# CPU_LPC1776.net
KiCad netlist of a schematic drawn in Altium Designer
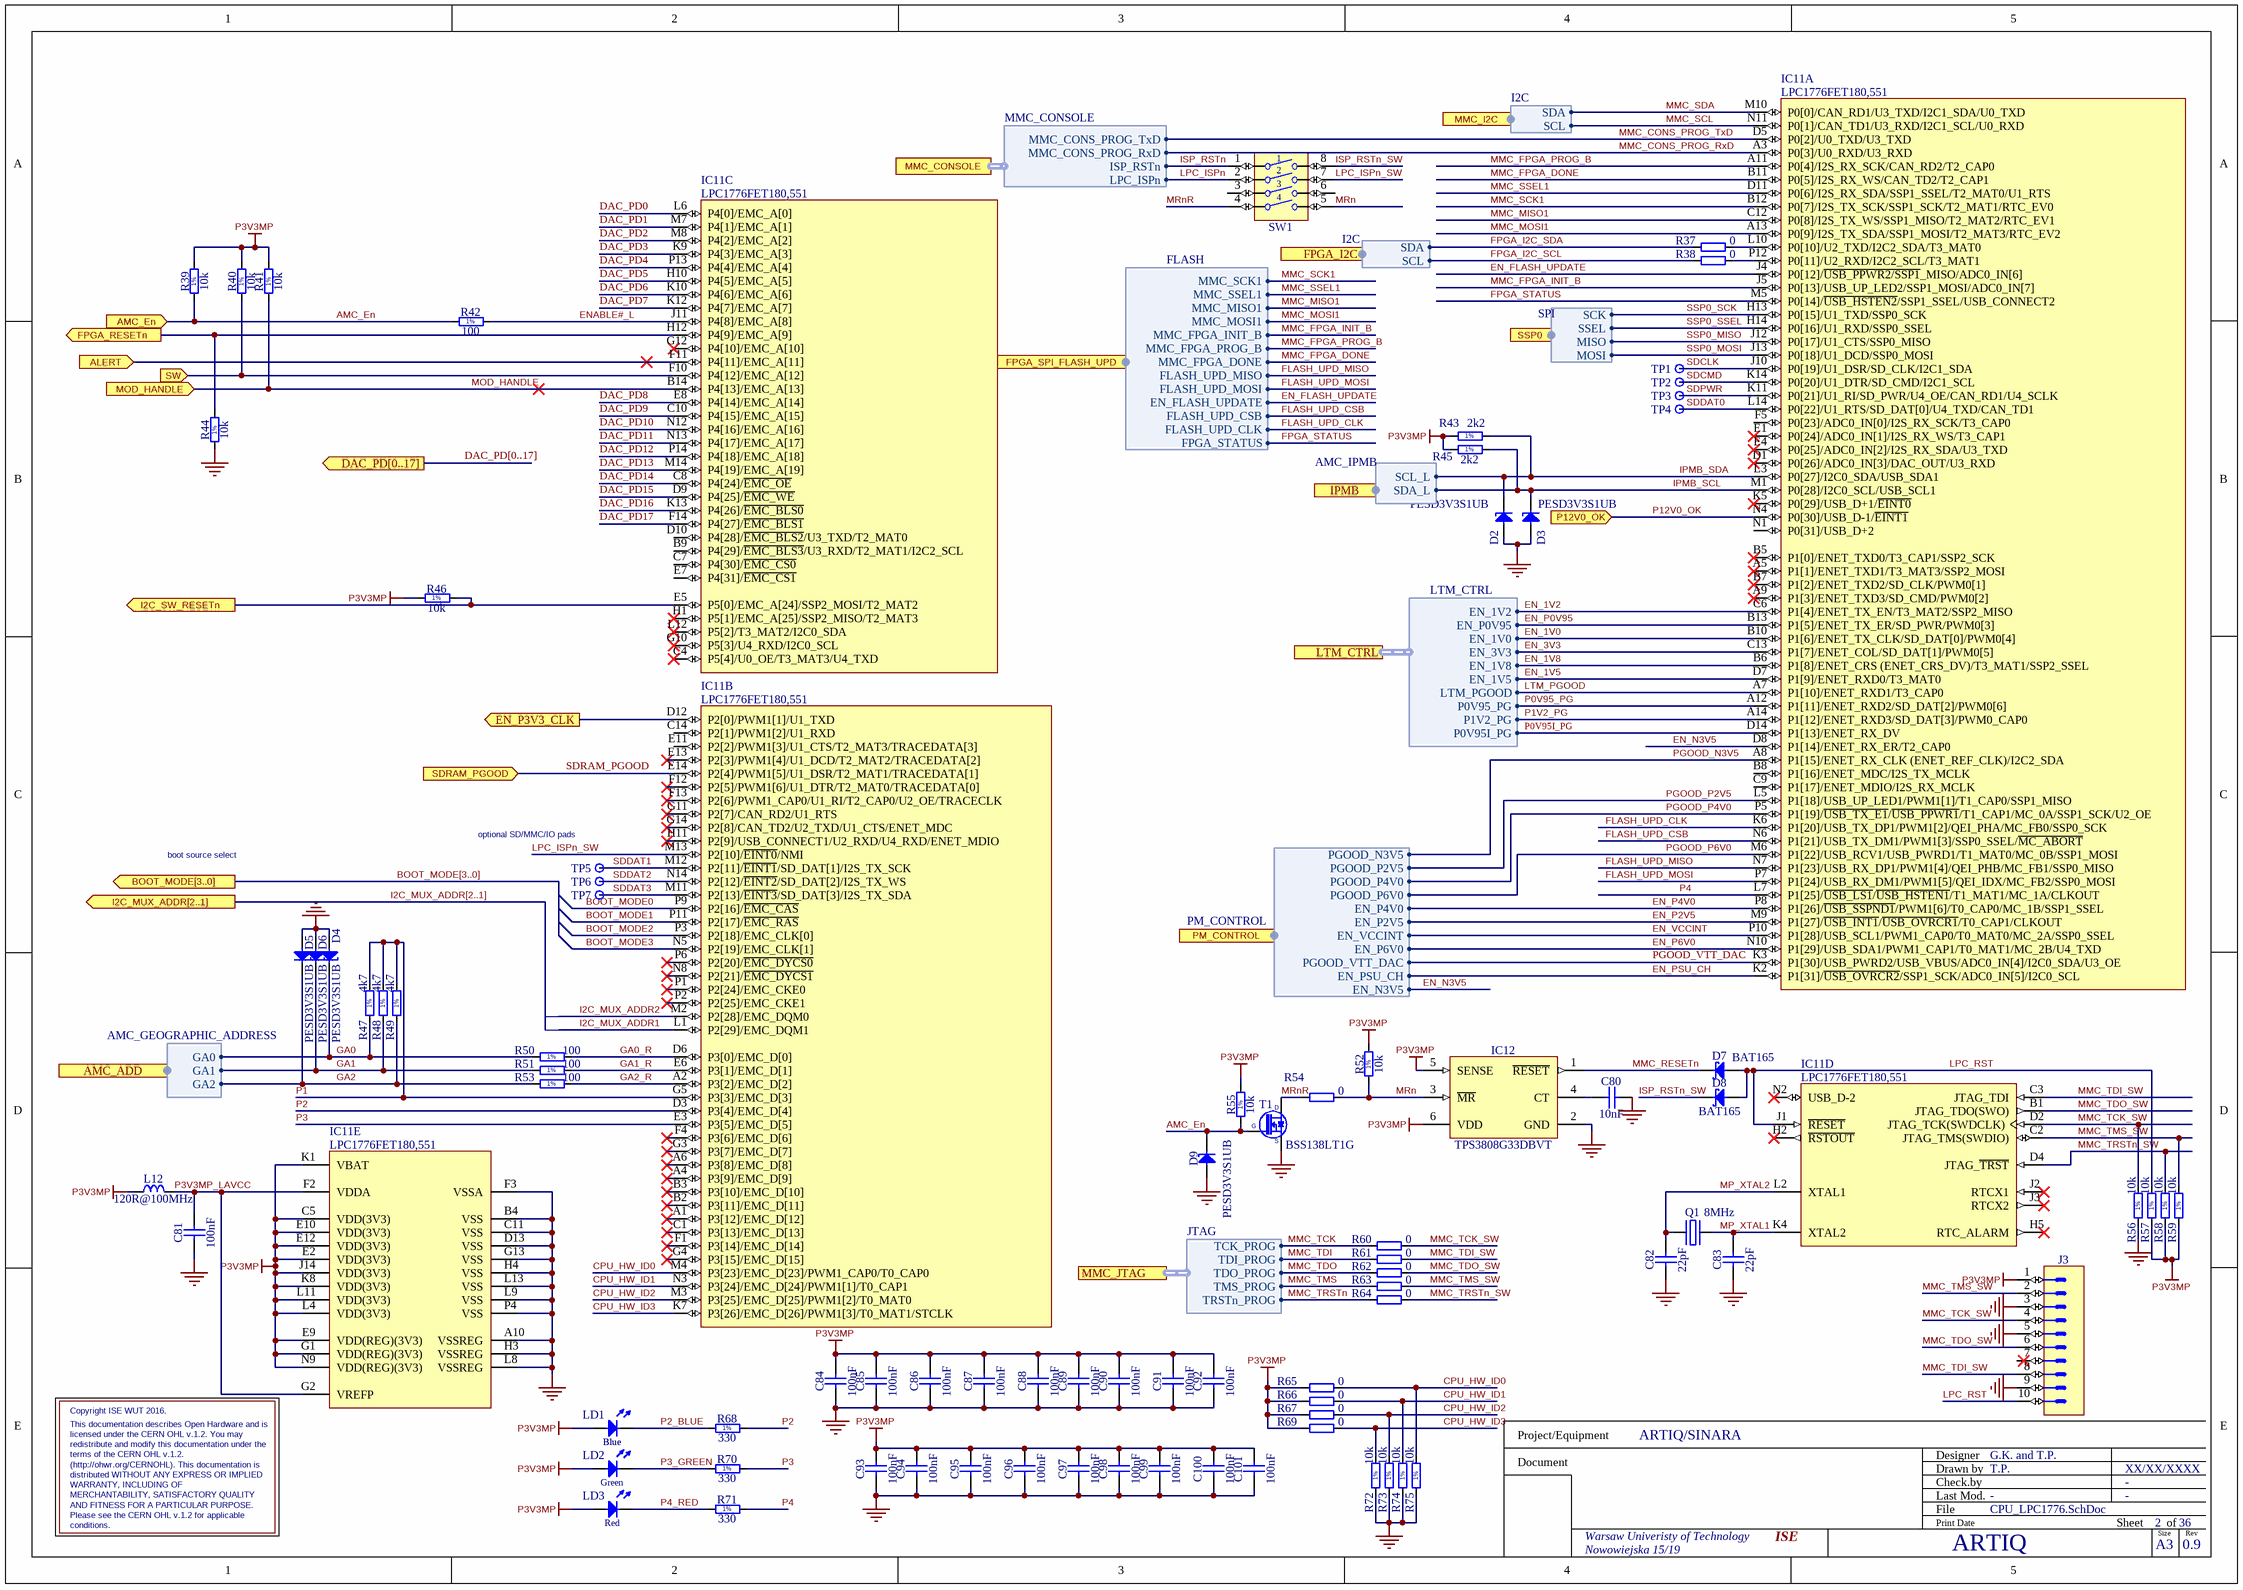
[diagram p0: CPU_LPC1776.SchDoc]

(export (version "E")
  (design (tool "Eeschema 10.0.6"))
  (components
    (comp (ref "C80")
      (value "10nF")
      (footprint "CAPC1005X55N")
      (description "Non-polarised capacitor")
      (fields
        (field (name "MANUFACTURER PART NUMBER") "CC0402_10NF_16V_10%_X7R")
        (field (name "MANUFACTURER") "GENERIC")
        (field (name "AUTHOR") "CERN DEM JLC")
      )
      (libsource (lib "Capacitors") (part "Capacitor - non polarized"))
    )
    (comp (ref "C81")
      (value "100nF")
      (footprint "CAPC0603X33N")
      (description "Non-polarised capacitor")
      (fields
        (field (name "MANUFACTURER PART NUMBER") "CC0201_100NF_6.3V_10%_X5R")
        (field (name "MANUFACTURER") "GENERIC")
        (field (name "AUTHOR") "CERN DEM JLC")
      )
      (libsource (lib "Capacitors") (part "Capacitor - non polarized"))
    )
    (comp (ref "C82")
      (value "22pF")
      (footprint "CAPC1005X55N")
      (description "Non-polarised capacitor")
      (fields
        (field (name "MANUFACTURER PART NUMBER") "CC0402_22PF_50V_5%_C0G")
        (field (name "MANUFACTURER") "GENERIC")
        (field (name "AUTHOR") "CERN DEM JLC")
      )
      (libsource (lib "Capacitors") (part "Capacitor - non polarized"))
    )
    (comp (ref "C83")
      (value "22pF")
      (footprint "CAPC1005X55N")
      (description "Non-polarised capacitor")
      (fields
        (field (name "MANUFACTURER PART NUMBER") "CC0402_22PF_50V_5%_C0G")
        (field (name "MANUFACTURER") "GENERIC")
        (field (name "AUTHOR") "CERN DEM JLC")
      )
      (libsource (lib "Capacitors") (part "Capacitor - non polarized"))
    )
    (comp (ref "C84")
      (value "100nF")
      (footprint "CAPC0603X33N")
      (description "Non-polarised capacitor")
      (fields
        (field (name "MANUFACTURER PART NUMBER") "CC0201_100NF_6.3V_10%_X5R")
        (field (name "MANUFACTURER") "GENERIC")
        (field (name "AUTHOR") "CERN DEM JLC")
      )
      (libsource (lib "Capacitors") (part "Capacitor - non polarized"))
    )
    (comp (ref "C85")
      (value "100nF")
      (footprint "CAPC0603X33N")
      (description "Non-polarised capacitor")
      (fields
        (field (name "MANUFACTURER PART NUMBER") "CC0201_100NF_6.3V_10%_X5R")
        (field (name "MANUFACTURER") "GENERIC")
        (field (name "AUTHOR") "CERN DEM JLC")
      )
      (libsource (lib "Capacitors") (part "Capacitor - non polarized"))
    )
    (comp (ref "C86")
      (value "100nF")
      (footprint "CAPC0603X33N")
      (description "Non-polarised capacitor")
      (fields
        (field (name "MANUFACTURER PART NUMBER") "CC0201_100NF_6.3V_10%_X5R")
        (field (name "MANUFACTURER") "GENERIC")
        (field (name "AUTHOR") "CERN DEM JLC")
      )
      (libsource (lib "Capacitors") (part "Capacitor - non polarized"))
    )
    (comp (ref "C87")
      (value "100nF")
      (footprint "CAPC0603X33N")
      (description "Non-polarised capacitor")
      (fields
        (field (name "MANUFACTURER PART NUMBER") "CC0201_100NF_6.3V_10%_X5R")
        (field (name "MANUFACTURER") "GENERIC")
        (field (name "AUTHOR") "CERN DEM JLC")
      )
      (libsource (lib "Capacitors") (part "Capacitor - non polarized"))
    )
    (comp (ref "C88")
      (value "100nF")
      (footprint "CAPC0603X33N")
      (description "Non-polarised capacitor")
      (fields
        (field (name "MANUFACTURER PART NUMBER") "CC0201_100NF_6.3V_10%_X5R")
        (field (name "MANUFACTURER") "GENERIC")
        (field (name "AUTHOR") "CERN DEM JLC")
      )
      (libsource (lib "Capacitors") (part "Capacitor - non polarized"))
    )
    (comp (ref "C89")
      (value "100nF")
      (footprint "CAPC0603X33N")
      (description "Non-polarised capacitor")
      (fields
        (field (name "MANUFACTURER PART NUMBER") "CC0201_100NF_6.3V_10%_X5R")
        (field (name "MANUFACTURER") "GENERIC")
        (field (name "AUTHOR") "CERN DEM JLC")
      )
      (libsource (lib "Capacitors") (part "Capacitor - non polarized"))
    )
    (comp (ref "C90")
      (value "100nF")
      (footprint "CAPC0603X33N")
      (description "Non-polarised capacitor")
      (fields
        (field (name "MANUFACTURER PART NUMBER") "CC0201_100NF_6.3V_10%_X5R")
        (field (name "MANUFACTURER") "GENERIC")
        (field (name "AUTHOR") "CERN DEM JLC")
      )
      (libsource (lib "Capacitors") (part "Capacitor - non polarized"))
    )
    (comp (ref "C91")
      (value "100nF")
      (footprint "CAPC0603X33N")
      (description "Non-polarised capacitor")
      (fields
        (field (name "MANUFACTURER PART NUMBER") "CC0201_100NF_6.3V_10%_X5R")
        (field (name "MANUFACTURER") "GENERIC")
        (field (name "AUTHOR") "CERN DEM JLC")
      )
      (libsource (lib "Capacitors") (part "Capacitor - non polarized"))
    )
    (comp (ref "C92")
      (value "100nF")
      (footprint "CAPC0603X33N")
      (description "Non-polarised capacitor")
      (fields
        (field (name "MANUFACTURER PART NUMBER") "CC0201_100NF_6.3V_10%_X5R")
        (field (name "MANUFACTURER") "GENERIC")
        (field (name "AUTHOR") "CERN DEM JLC")
      )
      (libsource (lib "Capacitors") (part "Capacitor - non polarized"))
    )
    (comp (ref "C93")
      (value "100nF")
      (footprint "CAPC0603X33N")
      (description "Non-polarised capacitor")
      (fields
        (field (name "MANUFACTURER PART NUMBER") "CC0201_100NF_6.3V_10%_X5R")
        (field (name "MANUFACTURER") "GENERIC")
        (field (name "AUTHOR") "CERN DEM JLC")
      )
      (libsource (lib "Capacitors") (part "Capacitor - non polarized"))
    )
    (comp (ref "C94")
      (value "100nF")
      (footprint "CAPC0603X33N")
      (description "Non-polarised capacitor")
      (fields
        (field (name "MANUFACTURER PART NUMBER") "CC0201_100NF_6.3V_10%_X5R")
        (field (name "MANUFACTURER") "GENERIC")
        (field (name "AUTHOR") "CERN DEM JLC")
      )
      (libsource (lib "Capacitors") (part "Capacitor - non polarized"))
    )
    (comp (ref "C95")
      (value "100nF")
      (footprint "CAPC0603X33N")
      (description "Non-polarised capacitor")
      (fields
        (field (name "MANUFACTURER PART NUMBER") "CC0201_100NF_6.3V_10%_X5R")
        (field (name "MANUFACTURER") "GENERIC")
        (field (name "AUTHOR") "CERN DEM JLC")
      )
      (libsource (lib "Capacitors") (part "Capacitor - non polarized"))
    )
    (comp (ref "C96")
      (value "100nF")
      (footprint "CAPC0603X33N")
      (description "Non-polarised capacitor")
      (fields
        (field (name "MANUFACTURER PART NUMBER") "CC0201_100NF_6.3V_10%_X5R")
        (field (name "MANUFACTURER") "GENERIC")
        (field (name "AUTHOR") "CERN DEM JLC")
      )
      (libsource (lib "Capacitors") (part "Capacitor - non polarized"))
    )
    (comp (ref "C97")
      (value "100nF")
      (footprint "CAPC0603X33N")
      (description "Non-polarised capacitor")
      (fields
        (field (name "MANUFACTURER PART NUMBER") "CC0201_100NF_6.3V_10%_X5R")
        (field (name "MANUFACTURER") "GENERIC")
        (field (name "AUTHOR") "CERN DEM JLC")
      )
      (libsource (lib "Capacitors") (part "Capacitor - non polarized"))
    )
    (comp (ref "C98")
      (value "100nF")
      (footprint "CAPC0603X33N")
      (description "Non-polarised capacitor")
      (fields
        (field (name "MANUFACTURER PART NUMBER") "CC0201_100NF_6.3V_10%_X5R")
        (field (name "MANUFACTURER") "GENERIC")
        (field (name "AUTHOR") "CERN DEM JLC")
      )
      (libsource (lib "Capacitors") (part "Capacitor - non polarized"))
    )
    (comp (ref "C99")
      (value "100nF")
      (footprint "CAPC0603X33N")
      (description "Non-polarised capacitor")
      (fields
        (field (name "MANUFACTURER PART NUMBER") "CC0201_100NF_6.3V_10%_X5R")
        (field (name "MANUFACTURER") "GENERIC")
        (field (name "AUTHOR") "CERN DEM JLC")
      )
      (libsource (lib "Capacitors") (part "Capacitor - non polarized"))
    )
    (comp (ref "C100")
      (value "100nF")
      (footprint "CAPC0603X33N")
      (description "Non-polarised capacitor")
      (fields
        (field (name "MANUFACTURER PART NUMBER") "CC0201_100NF_6.3V_10%_X5R")
        (field (name "MANUFACTURER") "GENERIC")
        (field (name "AUTHOR") "CERN DEM JLC")
      )
      (libsource (lib "Capacitors") (part "Capacitor - non polarized"))
    )
    (comp (ref "C101")
      (value "100nF")
      (footprint "CAPC0603X33N")
      (description "Non-polarised capacitor")
      (fields
        (field (name "MANUFACTURER PART NUMBER") "CC0201_100NF_6.3V_10%_X5R")
        (field (name "MANUFACTURER") "GENERIC")
        (field (name "AUTHOR") "CERN DEM JLC")
      )
      (libsource (lib "Capacitors") (part "Capacitor - non polarized"))
    )
    (comp (ref "D2")
      (value "PESD3V3S1UB")
      (footprint "SODFL1608X65N")
      (description "ESD protection diode")
      (fields
        (field (name "MANUFACTURER") "NXP SEMICONDUCTORS")
        (field (name "VOLTAGE") "3V3")
        (field (name "AUTHOR") "CERN DEM JLC")
      )
      (libsource (lib "ICs And Semiconductors") (part "Diode ESD"))
    )
    (comp (ref "D3")
      (value "PESD3V3S1UB")
      (footprint "SODFL1608X65N")
      (description "ESD protection diode")
      (fields
        (field (name "MANUFACTURER") "NXP SEMICONDUCTORS")
        (field (name "VOLTAGE") "3V3")
        (field (name "AUTHOR") "CERN DEM JLC")
      )
      (libsource (lib "ICs And Semiconductors") (part "Diode ESD"))
    )
    (comp (ref "D4")
      (value "PESD3V3S1UB")
      (footprint "SODFL1608X65N")
      (description "ESD protection diode")
      (fields
        (field (name "MANUFACTURER") "NXP SEMICONDUCTORS")
        (field (name "VOLTAGE") "3V3")
        (field (name "AUTHOR") "CERN DEM JLC")
      )
      (libsource (lib "ICs And Semiconductors") (part "Diode ESD"))
    )
    (comp (ref "D5")
      (value "PESD3V3S1UB")
      (footprint "SODFL1608X65N")
      (description "ESD protection diode")
      (fields
        (field (name "MANUFACTURER") "NXP SEMICONDUCTORS")
        (field (name "VOLTAGE") "3V3")
        (field (name "AUTHOR") "CERN DEM JLC")
      )
      (libsource (lib "ICs And Semiconductors") (part "Diode ESD"))
    )
    (comp (ref "D6")
      (value "PESD3V3S1UB")
      (footprint "SODFL1608X65N")
      (description "ESD protection diode")
      (fields
        (field (name "MANUFACTURER") "NXP SEMICONDUCTORS")
        (field (name "VOLTAGE") "3V3")
        (field (name "AUTHOR") "CERN DEM JLC")
      )
      (libsource (lib "ICs And Semiconductors") (part "Diode ESD"))
    )
    (comp (ref "D7")
      (value "BAT165")
      (footprint "SOD2512X110N")
      (description "Schottky Diode")
      (fields
        (field (name "MANUFACTURER") "INFINEON")
        (field (name "VOLTAGE") "40V")
        (field (name "AUTHOR") "CERN DEM JLC")
      )
      (libsource (lib "ICs And Semiconductors") (part "Diode Schottky"))
    )
    (comp (ref "D8")
      (value "BAT165")
      (footprint "SOD2512X110N")
      (description "Schottky Diode")
      (fields
        (field (name "MANUFACTURER") "INFINEON")
        (field (name "VOLTAGE") "40V")
        (field (name "AUTHOR") "CERN DEM JLC")
      )
      (libsource (lib "ICs And Semiconductors") (part "Diode Schottky"))
    )
    (comp (ref "D9")
      (value "PESD3V3S1UB")
      (footprint "SODFL1608X65N")
      (description "ESD protection diode")
      (fields
        (field (name "MANUFACTURER") "NXP SEMICONDUCTORS")
        (field (name "VOLTAGE") "3V3")
        (field (name "AUTHOR") "CERN DEM JLC")
      )
      (libsource (lib "ICs And Semiconductors") (part "Diode ESD"))
    )
    (comp (ref "IC11")
      (value "LPC1776FET180,551")
      (footprint "BGA180C80P14X14_1200X1200X120")
      (fields (field (name "MANUFACTURER") "NXP SEMICONDUCTORS") (field (name "AUTHOR") "CERN DEM JMW"))
      (libsource (lib "ICs And Semiconductors") (part "LPC1776FET180,551"))
    )
    (comp (ref "IC12")
      (value "TPS3808G33DBVT")
      (footprint "SOT95P280X145-6N")
      (description "Low Quiescent Current, Programmable-Delay Supervisory Circuit")
      (fields (field (name "MANUFACTURER") "TEXAS INSTRUMENTS") (field (name "AUTHOR") "CERN DEM JLC"))
      (libsource (lib "ICs And Semiconductors") (part "TPS3808xxxDBV"))
    )
    (comp (ref "J3")
      (value "Header 10")
      (footprint "SAMTEC_FTS-105-02-F-DV")
      (description "Connector 10 Male")
      (fields
        (field (name "MANUFACTURER PART NUMBER") "FTS-105-02-F-DV")
        (field (name "MANUFACTURER") "SAMTEC")
        (field (name "AUTHOR") "CERN DEM JLC")
      )
      (libsource (lib "Connectors") (part "Connector 10 Male"))
    )
    (comp (ref "L12")
      (value "120R@100MHz")
      (footprint "INDC1608X95N")
      (description "Inductor")
      (fields
        (field (name "MANUFACTURER PART NUMBER") "BLM18PG121SN1D")
        (field (name "MANUFACTURER") "MURATA")
        (field (name "AUTHOR") "CERN DEM BC")
      )
      (libsource (lib "Inductors & Transformers") (part "Inductor"))
    )
    (comp (ref "LD1")
      (value "Blue")
      (footprint "LED_AVAGO_HSMR-C120")
      (description "LED Blue 1C 2A")
      (fields
        (field (name "MANUFACTURER PART NUMBER") "HSMR-C120")
        (field (name "MANUFACTURER") "AVAGO TECHNOLOGIES")
        (field (name "AUTHOR") "CERN DEM JLC")
      )
      (libsource (lib "ICs And Semiconductors") (part "LED Blue 1C 2A"))
    )
    (comp (ref "LD2")
      (value "Green")
      (footprint "LED_AVAGO_HSME-C120")
      (description "LED Green 1C 2A")
      (fields
        (field (name "MANUFACTURER PART NUMBER") "HSME-C120")
        (field (name "MANUFACTURER") "AVAGO TECHNOLOGIES")
        (field (name "AUTHOR") "CERN DEM JMW")
      )
      (libsource (lib "ICs And Semiconductors") (part "LED Green 1C 2A"))
    )
    (comp (ref "LD3")
      (value "Red")
      (footprint "LED_OSRAM_LS Q976")
      (description "LED Red 1C 2A")
      (fields
        (field (name "MANUFACTURER PART NUMBER") "LS Q976-NR-1")
        (field (name "MANUFACTURER") "OSRAM")
        (field (name "AUTHOR") "CERN DEM JLC")
      )
      (libsource (lib "ICs And Semiconductors") (part "LED Red 1C 2A"))
    )
    (comp (ref "Q1")
      (value "8MHz")
      (footprint "XTAL_TXC_7A")
      (description "Quartz Crystal")
      (fields
        (field (name "MANUFACTURER PART NUMBER") "7A-8.000MAAE-T")
        (field (name "MANUFACTURER") "TXC CORPORATION")
        (field (name "AUTHOR") "CERN DEM JLC")
      )
      (libsource (lib "ICs And Semiconductors") (part "Quartz Crystal"))
    )
    (comp (ref "R37")
      (value "0")
      (footprint "RESC1005X40N")
      (description "Resistor")
      (fields
        (field (name "MANUFACTURER PART NUMBER") "R0402_0R_JUMPER")
        (field (name "MANUFACTURER") "GENERIC")
        (field (name "AUTHOR") "CERN DEM JLC")
      )
      (libsource (lib "Resistors") (part "Resistor"))
    )
    (comp (ref "R38")
      (value "0")
      (footprint "RESC1005X40N")
      (description "Resistor")
      (fields
        (field (name "MANUFACTURER PART NUMBER") "R0402_0R_JUMPER")
        (field (name "MANUFACTURER") "GENERIC")
        (field (name "AUTHOR") "CERN DEM JLC")
      )
      (libsource (lib "Resistors") (part "Resistor"))
    )
    (comp (ref "R39")
      (value "10k")
      (footprint "RESC1005X40N")
      (description "Resistor - 1%")
      (fields
        (field (name "MANUFACTURER PART NUMBER") "R0402_10K_1%_0.0625W_100PPM")
        (field (name "MANUFACTURER") "GENERIC")
        (field (name "AUTHOR") "CERN DEM JLC")
      )
      (libsource (lib "Resistors") (part "Resistor - 1%"))
    )
    (comp (ref "R40")
      (value "10k")
      (footprint "RESC1005X40N")
      (description "Resistor - 1%")
      (fields
        (field (name "MANUFACTURER PART NUMBER") "R0402_10K_1%_0.0625W_100PPM")
        (field (name "MANUFACTURER") "GENERIC")
        (field (name "AUTHOR") "CERN DEM JLC")
      )
      (libsource (lib "Resistors") (part "Resistor - 1%"))
    )
    (comp (ref "R41")
      (value "10k")
      (footprint "RESC1005X40N")
      (description "Resistor - 1%")
      (fields
        (field (name "MANUFACTURER PART NUMBER") "R0402_10K_1%_0.0625W_100PPM")
        (field (name "MANUFACTURER") "GENERIC")
        (field (name "AUTHOR") "CERN DEM JLC")
      )
      (libsource (lib "Resistors") (part "Resistor - 1%"))
    )
    (comp (ref "R42")
      (value "100")
      (footprint "RESC1005X40N")
      (description "Resistor - 1%")
      (fields
        (field (name "MANUFACTURER PART NUMBER") "R0402_100R_1%_0.1W_100PPM_50V")
        (field (name "MANUFACTURER") "GENERIC")
        (field (name "AUTHOR") "CERN DEM JLC")
      )
      (libsource (lib "Resistors") (part "Resistor - 1%"))
    )
    (comp (ref "R43")
      (value "2k2")
      (footprint "RESC1005X40N")
      (description "Resistor - 1%")
      (fields
        (field (name "MANUFACTURER PART NUMBER") "R0402_2K2_1%_0.0625W_100PPM")
        (field (name "MANUFACTURER") "GENERIC")
        (field (name "AUTHOR") "CERN DEM JLC")
      )
      (libsource (lib "Resistors") (part "Resistor - 1%"))
    )
    (comp (ref "R44")
      (value "10k")
      (footprint "RESC1005X40N")
      (description "Resistor - 1%")
      (fields
        (field (name "MANUFACTURER PART NUMBER") "R0402_10K_1%_0.0625W_100PPM")
        (field (name "MANUFACTURER") "GENERIC")
        (field (name "AUTHOR") "CERN DEM JLC")
      )
      (libsource (lib "Resistors") (part "Resistor - 1%"))
    )
    (comp (ref "R45")
      (value "2k2")
      (footprint "RESC1005X40N")
      (description "Resistor - 1%")
      (fields
        (field (name "MANUFACTURER PART NUMBER") "R0402_2K2_1%_0.0625W_100PPM")
        (field (name "MANUFACTURER") "GENERIC")
        (field (name "AUTHOR") "CERN DEM JLC")
      )
      (libsource (lib "Resistors") (part "Resistor - 1%"))
    )
    (comp (ref "R46")
      (value "10k")
      (footprint "RESC1005X40N")
      (description "Resistor - 1%")
      (fields
        (field (name "MANUFACTURER PART NUMBER") "R0402_10K_1%_0.0625W_100PPM")
        (field (name "MANUFACTURER") "GENERIC")
        (field (name "AUTHOR") "CERN DEM JLC")
      )
      (libsource (lib "Resistors") (part "Resistor - 1%"))
    )
    (comp (ref "R47")
      (value "4k7")
      (footprint "RESC1005X40N")
      (description "Resistor - 1%")
      (fields
        (field (name "MANUFACTURER PART NUMBER") "R0402_4K7_1%_0.0625W_100PPM")
        (field (name "MANUFACTURER") "GENERIC")
        (field (name "AUTHOR") "CERN DEM JLC")
      )
      (libsource (lib "Resistors") (part "Resistor - 1%"))
    )
    (comp (ref "R48")
      (value "4k7")
      (footprint "RESC1005X40N")
      (description "Resistor - 1%")
      (fields
        (field (name "MANUFACTURER PART NUMBER") "R0402_4K7_1%_0.0625W_100PPM")
        (field (name "MANUFACTURER") "GENERIC")
        (field (name "AUTHOR") "CERN DEM JLC")
      )
      (libsource (lib "Resistors") (part "Resistor - 1%"))
    )
    (comp (ref "R49")
      (value "4k7")
      (footprint "RESC1005X40N")
      (description "Resistor - 1%")
      (fields
        (field (name "MANUFACTURER PART NUMBER") "R0402_4K7_1%_0.0625W_100PPM")
        (field (name "MANUFACTURER") "GENERIC")
        (field (name "AUTHOR") "CERN DEM JLC")
      )
      (libsource (lib "Resistors") (part "Resistor - 1%"))
    )
    (comp (ref "R50")
      (value "100")
      (footprint "RESC1005X40N")
      (description "Resistor - 1%")
      (fields
        (field (name "MANUFACTURER PART NUMBER") "R0402_100R_1%_0.1W_100PPM_50V")
        (field (name "MANUFACTURER") "GENERIC")
        (field (name "AUTHOR") "CERN DEM JLC")
      )
      (libsource (lib "Resistors") (part "Resistor - 1%"))
    )
    (comp (ref "R51")
      (value "100")
      (footprint "RESC1005X40N")
      (description "Resistor - 1%")
      (fields
        (field (name "MANUFACTURER PART NUMBER") "R0402_100R_1%_0.1W_100PPM_50V")
        (field (name "MANUFACTURER") "GENERIC")
        (field (name "AUTHOR") "CERN DEM JLC")
      )
      (libsource (lib "Resistors") (part "Resistor - 1%"))
    )
    (comp (ref "R52")
      (value "10k")
      (footprint "RESC1005X40N")
      (description "Resistor - 1%")
      (fields
        (field (name "MANUFACTURER PART NUMBER") "R0402_10K_1%_0.0625W_100PPM")
        (field (name "MANUFACTURER") "GENERIC")
        (field (name "AUTHOR") "CERN DEM JLC")
      )
      (libsource (lib "Resistors") (part "Resistor - 1%"))
    )
    (comp (ref "R53")
      (value "100")
      (footprint "RESC1005X40N")
      (description "Resistor - 1%")
      (fields
        (field (name "MANUFACTURER PART NUMBER") "R0402_100R_1%_0.1W_100PPM_50V")
        (field (name "MANUFACTURER") "GENERIC")
        (field (name "AUTHOR") "CERN DEM JLC")
      )
      (libsource (lib "Resistors") (part "Resistor - 1%"))
    )
    (comp (ref "R54")
      (value "0")
      (footprint "RESC1005X40N")
      (description "Resistor")
      (fields
        (field (name "MANUFACTURER PART NUMBER") "R0402_0R_JUMPER")
        (field (name "MANUFACTURER") "GENERIC")
        (field (name "AUTHOR") "CERN DEM JLC")
      )
      (libsource (lib "Resistors") (part "Resistor"))
    )
    (comp (ref "R55")
      (value "10k")
      (footprint "RESC1005X40N")
      (description "Resistor - 1%")
      (fields
        (field (name "MANUFACTURER PART NUMBER") "R0402_10K_1%_0.0625W_100PPM")
        (field (name "MANUFACTURER") "GENERIC")
        (field (name "AUTHOR") "CERN DEM JLC")
      )
      (libsource (lib "Resistors") (part "Resistor - 1%"))
    )
    (comp (ref "R56")
      (value "10k")
      (footprint "RESC1005X40N")
      (description "Resistor - 1%")
      (fields
        (field (name "MANUFACTURER PART NUMBER") "R0402_10K_1%_0.0625W_100PPM")
        (field (name "MANUFACTURER") "GENERIC")
        (field (name "AUTHOR") "CERN DEM JLC")
      )
      (libsource (lib "Resistors") (part "Resistor - 1%"))
    )
    (comp (ref "R57")
      (value "10k")
      (footprint "RESC1005X40N")
      (description "Resistor - 1%")
      (fields
        (field (name "MANUFACTURER PART NUMBER") "R0402_10K_1%_0.0625W_100PPM")
        (field (name "MANUFACTURER") "GENERIC")
        (field (name "AUTHOR") "CERN DEM JLC")
      )
      (libsource (lib "Resistors") (part "Resistor - 1%"))
    )
    (comp (ref "R58")
      (value "10k")
      (footprint "RESC1005X40N")
      (description "Resistor - 1%")
      (fields
        (field (name "MANUFACTURER PART NUMBER") "R0402_10K_1%_0.0625W_100PPM")
        (field (name "MANUFACTURER") "GENERIC")
        (field (name "AUTHOR") "CERN DEM JLC")
      )
      (libsource (lib "Resistors") (part "Resistor - 1%"))
    )
    (comp (ref "R59")
      (value "10k")
      (footprint "RESC1005X40N")
      (description "Resistor - 1%")
      (fields
        (field (name "MANUFACTURER PART NUMBER") "R0402_10K_1%_0.0625W_100PPM")
        (field (name "MANUFACTURER") "GENERIC")
        (field (name "AUTHOR") "CERN DEM JLC")
      )
      (libsource (lib "Resistors") (part "Resistor - 1%"))
    )
    (comp (ref "R60")
      (value "0")
      (footprint "RESC1005X40N")
      (description "Resistor")
      (fields
        (field (name "MANUFACTURER PART NUMBER") "R0402_0R_JUMPER")
        (field (name "MANUFACTURER") "GENERIC")
        (field (name "AUTHOR") "CERN DEM JLC")
      )
      (libsource (lib "Resistors") (part "Resistor"))
    )
    (comp (ref "R61")
      (value "0")
      (footprint "RESC1005X40N")
      (description "Resistor")
      (fields
        (field (name "MANUFACTURER PART NUMBER") "R0402_0R_JUMPER")
        (field (name "MANUFACTURER") "GENERIC")
        (field (name "AUTHOR") "CERN DEM JLC")
      )
      (libsource (lib "Resistors") (part "Resistor"))
    )
    (comp (ref "R62")
      (value "0")
      (footprint "RESC1005X40N")
      (description "Resistor")
      (fields
        (field (name "MANUFACTURER PART NUMBER") "R0402_0R_JUMPER")
        (field (name "MANUFACTURER") "GENERIC")
        (field (name "AUTHOR") "CERN DEM JLC")
      )
      (libsource (lib "Resistors") (part "Resistor"))
    )
    (comp (ref "R63")
      (value "0")
      (footprint "RESC1005X40N")
      (description "Resistor")
      (fields
        (field (name "MANUFACTURER PART NUMBER") "R0402_0R_JUMPER")
        (field (name "MANUFACTURER") "GENERIC")
        (field (name "AUTHOR") "CERN DEM JLC")
      )
      (libsource (lib "Resistors") (part "Resistor"))
    )
    (comp (ref "R64")
      (value "0")
      (footprint "RESC1005X40N")
      (description "Resistor")
      (fields
        (field (name "MANUFACTURER PART NUMBER") "R0402_0R_JUMPER")
        (field (name "MANUFACTURER") "GENERIC")
        (field (name "AUTHOR") "CERN DEM JLC")
      )
      (libsource (lib "Resistors") (part "Resistor"))
    )
    (comp (ref "R65")
      (value "0")
      (footprint "RESC1005X40N")
      (description "Resistor")
      (fields
        (field (name "MANUFACTURER PART NUMBER") "R0402_0R_JUMPER")
        (field (name "MANUFACTURER") "GENERIC")
        (field (name "AUTHOR") "CERN DEM JLC")
      )
      (libsource (lib "Resistors") (part "Resistor"))
    )
    (comp (ref "R66")
      (value "0")
      (footprint "RESC1005X40N")
      (description "Resistor")
      (fields
        (field (name "MANUFACTURER PART NUMBER") "R0402_0R_JUMPER")
        (field (name "MANUFACTURER") "GENERIC")
        (field (name "AUTHOR") "CERN DEM JLC")
      )
      (libsource (lib "Resistors") (part "Resistor"))
    )
    (comp (ref "R67")
      (value "0")
      (footprint "RESC1005X40N")
      (description "Resistor")
      (fields
        (field (name "MANUFACTURER PART NUMBER") "R0402_0R_JUMPER")
        (field (name "MANUFACTURER") "GENERIC")
        (field (name "AUTHOR") "CERN DEM JLC")
      )
      (libsource (lib "Resistors") (part "Resistor"))
    )
    (comp (ref "R68")
      (value "330")
      (footprint "RESC1005X40N")
      (description "Resistor - 1%")
      (fields
        (field (name "MANUFACTURER PART NUMBER") "R0402_330R_1%_0.0625W_100PPM")
        (field (name "MANUFACTURER") "GENERIC")
        (field (name "AUTHOR") "CERN DEM JLC")
      )
      (libsource (lib "Resistors") (part "Resistor - 1%"))
    )
    (comp (ref "R69")
      (value "0")
      (footprint "RESC1005X40N")
      (description "Resistor")
      (fields
        (field (name "MANUFACTURER PART NUMBER") "R0402_0R_JUMPER")
        (field (name "MANUFACTURER") "GENERIC")
        (field (name "AUTHOR") "CERN DEM JLC")
      )
      (libsource (lib "Resistors") (part "Resistor"))
    )
    (comp (ref "R70")
      (value "330")
      (footprint "RESC1005X40N")
      (description "Resistor - 1%")
      (fields
        (field (name "MANUFACTURER PART NUMBER") "R0402_330R_1%_0.0625W_100PPM")
        (field (name "MANUFACTURER") "GENERIC")
        (field (name "AUTHOR") "CERN DEM JLC")
      )
      (libsource (lib "Resistors") (part "Resistor - 1%"))
    )
    (comp (ref "R71")
      (value "330")
      (footprint "RESC1005X40N")
      (description "Resistor - 1%")
      (fields
        (field (name "MANUFACTURER PART NUMBER") "R0402_330R_1%_0.0625W_100PPM")
        (field (name "MANUFACTURER") "GENERIC")
        (field (name "AUTHOR") "CERN DEM JLC")
      )
      (libsource (lib "Resistors") (part "Resistor - 1%"))
    )
    (comp (ref "R72")
      (value "10k")
      (footprint "RESC1005X40N")
      (description "Resistor - 1%")
      (fields
        (field (name "MANUFACTURER PART NUMBER") "R0402_10K_1%_0.0625W_100PPM")
        (field (name "MANUFACTURER") "GENERIC")
        (field (name "AUTHOR") "CERN DEM JLC")
      )
      (libsource (lib "Resistors") (part "Resistor - 1%"))
    )
    (comp (ref "R73")
      (value "10k")
      (footprint "RESC1005X40N")
      (description "Resistor - 1%")
      (fields
        (field (name "MANUFACTURER PART NUMBER") "R0402_10K_1%_0.0625W_100PPM")
        (field (name "MANUFACTURER") "GENERIC")
        (field (name "AUTHOR") "CERN DEM JLC")
      )
      (libsource (lib "Resistors") (part "Resistor - 1%"))
    )
    (comp (ref "R74")
      (value "10k")
      (footprint "RESC1005X40N")
      (description "Resistor - 1%")
      (fields
        (field (name "MANUFACTURER PART NUMBER") "R0402_10K_1%_0.0625W_100PPM")
        (field (name "MANUFACTURER") "GENERIC")
        (field (name "AUTHOR") "CERN DEM JLC")
      )
      (libsource (lib "Resistors") (part "Resistor - 1%"))
    )
    (comp (ref "R75")
      (value "10k")
      (footprint "RESC1005X40N")
      (description "Resistor - 1%")
      (fields
        (field (name "MANUFACTURER PART NUMBER") "R0402_10K_1%_0.0625W_100PPM")
        (field (name "MANUFACTURER") "GENERIC")
        (field (name "AUTHOR") "CERN DEM JLC")
      )
      (libsource (lib "Resistors") (part "Resistor - 1%"))
    )
    (comp (ref "SW1")
      (value "Switch")
      (footprint "SW_TYCO_1571983-4")
      (description "4 Ways SPST DIP Switch")
      (fields
        (field (name "PART NUMBER") "SW_TYCO_1571983-4")
        (field (name "MANUFACTURER") "TYCO")
        (field (name "AUTHOR") "CERN DEM JLC")
      )
      (libsource (lib "Eletro-mechanical") (part "SW 4x SPST DIP Switch"))
    )
    (comp (ref "T1")
      (value "BSS138LT1G")
      (footprint "SOT95P240X110-3N")
      (description "N-CHANNEL MOSFET WITH DIODE")
      (fields (field (name "MANUFACTURER") "ON SEMICONDUCTOR") (field (name "AUTHOR") "CERN DEM JLC"))
      (libsource (lib "ICs And Semiconductors") (part "N-MOSFET-D 1G 2S 3D"))
    )
    (comp (ref "TP1")
      (value "Test Point")
      (footprint "TPS127")
      (fields (field (name "PART NUMBER") "SMD_PAD_1.27X1.27MM") (field (name "AUTHOR") "CERN DEM JLC"))
      (libsource (lib "Eletro-mechanical") (part "Test Point"))
    )
    (comp (ref "TP2")
      (value "Test Point")
      (footprint "TPS127")
      (fields (field (name "PART NUMBER") "SMD_PAD_1.27X1.27MM") (field (name "AUTHOR") "CERN DEM JLC"))
      (libsource (lib "Eletro-mechanical") (part "Test Point"))
    )
    (comp (ref "TP3")
      (value "Test Point")
      (footprint "TPS127")
      (fields (field (name "PART NUMBER") "SMD_PAD_1.27X1.27MM") (field (name "AUTHOR") "CERN DEM JLC"))
      (libsource (lib "Eletro-mechanical") (part "Test Point"))
    )
    (comp (ref "TP4")
      (value "Test Point")
      (footprint "TPS127")
      (fields (field (name "PART NUMBER") "SMD_PAD_1.27X1.27MM") (field (name "AUTHOR") "CERN DEM JLC"))
      (libsource (lib "Eletro-mechanical") (part "Test Point"))
    )
    (comp (ref "TP5")
      (value "Test Point")
      (footprint "TPS127")
      (fields (field (name "PART NUMBER") "SMD_PAD_1.27X1.27MM") (field (name "AUTHOR") "CERN DEM JLC"))
      (libsource (lib "Eletro-mechanical") (part "Test Point"))
    )
    (comp (ref "TP6")
      (value "Test Point")
      (footprint "TPS127")
      (fields (field (name "PART NUMBER") "SMD_PAD_1.27X1.27MM") (field (name "AUTHOR") "CERN DEM JLC"))
      (libsource (lib "Eletro-mechanical") (part "Test Point"))
    )
    (comp (ref "TP7")
      (value "Test Point")
      (footprint "TPS127")
      (fields (field (name "PART NUMBER") "SMD_PAD_1.27X1.27MM") (field (name "AUTHOR") "CERN DEM JLC"))
      (libsource (lib "Eletro-mechanical") (part "Test Point"))
    )
  )
  (nets
    (net (code "10") (name "/ALERT") (class "Default")
      (node (ref "IC11") (pin "F11") (pinfunction "P4[11]/EMC_A[11]_F11") (pintype "bidirectional"))
    )
    (net (code "11") (name "/AMC_En") (class "Default")
      (node (ref "D9") (pin "1") (pinfunction "C_1") (pintype "passive"))
      (node (ref "R39") (pin "1") (pinfunction "1_1") (pintype "passive"))
      (node (ref "R42") (pin "1") (pinfunction "1_1") (pintype "passive"))
      (node (ref "R55") (pin "1") (pinfunction "1_1") (pintype "passive"))
      (node (ref "T1") (pin "1") (pinfunction "G_1") (pintype "passive"))
    )
    (net (code "12") (name "/BOOT_MODE0") (class "Default")
      (node (ref "IC11") (pin "P9") (pinfunction "P2[16]/~{EMC_CAS}_P9") (pintype "bidirectional"))
    )
    (net (code "13") (name "/BOOT_MODE1") (class "Default")
      (node (ref "IC11") (pin "P11") (pinfunction "P2[17]/~{EMC_RAS}_P11") (pintype "bidirectional"))
    )
    (net (code "14") (name "/BOOT_MODE2") (class "Default")
      (node (ref "IC11") (pin "P3") (pinfunction "P2[18]/EMC_CLK[0]_P3") (pintype "bidirectional"))
    )
    (net (code "15") (name "/BOOT_MODE3") (class "Default")
      (node (ref "IC11") (pin "N5") (pinfunction "P2[19]/EMC_CLK[1]_N5") (pintype "bidirectional"))
    )
    (net (code "17") (name "/CPU_HW_ID0") (class "Default")
      (node (ref "IC11") (pin "M4") (pinfunction "P3[23]/EMC_D[23]/PWM1_CAP0/T0_CAP0_M4") (pintype "bidirectional"))
      (node (ref "R65") (pin "2") (pinfunction "2_2") (pintype "passive"))
      (node (ref "R75") (pin "2") (pinfunction "2_2") (pintype "passive"))
    )
    (net (code "18") (name "/CPU_HW_ID1") (class "Default")
      (node (ref "IC11") (pin "N3") (pinfunction "P3[24]/EMC_D[24]/PWM1[1]/T0_CAP1_N3") (pintype "bidirectional"))
      (node (ref "R66") (pin "2") (pinfunction "2_2") (pintype "passive"))
      (node (ref "R74") (pin "2") (pinfunction "2_2") (pintype "passive"))
    )
    (net (code "19") (name "/CPU_HW_ID2") (class "Default")
      (node (ref "IC11") (pin "M3") (pinfunction "P3[25]/EMC_D[25]/PWM1[2]/T0_MAT0_M3") (pintype "bidirectional"))
      (node (ref "R67") (pin "2") (pinfunction "2_2") (pintype "passive"))
      (node (ref "R73") (pin "2") (pinfunction "2_2") (pintype "passive"))
    )
    (net (code "20") (name "/CPU_HW_ID3") (class "Default")
      (node (ref "IC11") (pin "K7") (pinfunction "P3[26]/EMC_D[26]/PWM1[3]/T0_MAT1/STCLK_K7") (pintype "bidirectional"))
      (node (ref "R69") (pin "2") (pinfunction "2_2") (pintype "passive"))
      (node (ref "R72") (pin "2") (pinfunction "2_2") (pintype "passive"))
    )
    (net (code "21") (name "/DAC_PD0") (class "Default")
      (node (ref "IC11") (pin "L6") (pinfunction "P4[0]/EMC_A[0]_L6") (pintype "bidirectional"))
    )
    (net (code "22") (name "/DAC_PD1") (class "Default")
      (node (ref "IC11") (pin "M7") (pinfunction "P4[1]/EMC_A[1]_M7") (pintype "bidirectional"))
    )
    (net (code "23") (name "/DAC_PD2") (class "Default")
      (node (ref "IC11") (pin "M8") (pinfunction "P4[2]/EMC_A[2]_M8") (pintype "bidirectional"))
    )
    (net (code "24") (name "/DAC_PD3") (class "Default")
      (node (ref "IC11") (pin "K9") (pinfunction "P4[3]/EMC_A[3]_K9") (pintype "bidirectional"))
    )
    (net (code "25") (name "/DAC_PD4") (class "Default")
      (node (ref "IC11") (pin "P13") (pinfunction "P4[4]/EMC_A[4]_P13") (pintype "bidirectional"))
    )
    (net (code "26") (name "/DAC_PD5") (class "Default")
      (node (ref "IC11") (pin "H10") (pinfunction "P4[5]/EMC_A[5]_H10") (pintype "bidirectional"))
    )
    (net (code "27") (name "/DAC_PD6") (class "Default")
      (node (ref "IC11") (pin "K10") (pinfunction "P4[6]/EMC_A[6]_K10") (pintype "bidirectional"))
    )
    (net (code "28") (name "/DAC_PD7") (class "Default")
      (node (ref "IC11") (pin "K12") (pinfunction "P4[7]/EMC_A[7]_K12") (pintype "bidirectional"))
    )
    (net (code "29") (name "/DAC_PD8") (class "Default")
      (node (ref "IC11") (pin "E8") (pinfunction "P4[14]/EMC_A[14]_E8") (pintype "bidirectional"))
    )
    (net (code "30") (name "/DAC_PD9") (class "Default")
      (node (ref "IC11") (pin "C10") (pinfunction "P4[15]/EMC_A[15]_C10") (pintype "bidirectional"))
    )
    (net (code "31") (name "/DAC_PD10") (class "Default")
      (node (ref "IC11") (pin "N12") (pinfunction "P4[16]/EMC_A[16]_N12") (pintype "bidirectional"))
    )
    (net (code "32") (name "/DAC_PD11") (class "Default")
      (node (ref "IC11") (pin "N13") (pinfunction "P4[17]/EMC_A[17]_N13") (pintype "bidirectional"))
    )
    (net (code "33") (name "/DAC_PD12") (class "Default")
      (node (ref "IC11") (pin "P14") (pinfunction "P4[18]/EMC_A[18]_P14") (pintype "bidirectional"))
    )
    (net (code "34") (name "/DAC_PD13") (class "Default")
      (node (ref "IC11") (pin "M14") (pinfunction "P4[19]/EMC_A[19]_M14") (pintype "bidirectional"))
    )
    (net (code "35") (name "/DAC_PD14") (class "Default")
      (node (ref "IC11") (pin "C8") (pinfunction "P4[24]/~{EMC_OE}_C8") (pintype "bidirectional"))
    )
    (net (code "36") (name "/DAC_PD15") (class "Default")
      (node (ref "IC11") (pin "D9") (pinfunction "P4[25]/~{EMC_WE}_D9") (pintype "bidirectional"))
    )
    (net (code "37") (name "/DAC_PD16") (class "Default")
      (node (ref "IC11") (pin "K13") (pinfunction "P4[26]/~{EMC_BLS0}_K13") (pintype "bidirectional"))
    )
    (net (code "38") (name "/DAC_PD17") (class "Default")
      (node (ref "IC11") (pin "F14") (pinfunction "P4[27]/~{EMC_BLS1}_F14") (pintype "bidirectional"))
    )
    (net (code "40") (name "/ENABLE#_L") (class "Default")
      (node (ref "IC11") (pin "J11") (pinfunction "P4[8]/EMC_A[8]_J11") (pintype "bidirectional"))
      (node (ref "R42") (pin "2") (pinfunction "2_2") (pintype "passive"))
    )
    (net (code "41") (name "/EN_1V0") (class "Default")
      (node (ref "IC11") (pin "B10") (pinfunction "P1[6]/ENET_TX_CLK/SD_DAT[0]/PWM0[4]_B10") (pintype "bidirectional"))
    )
    (net (code "42") (name "/EN_1V2") (class "Default")
      (node (ref "IC11") (pin "C6") (pinfunction "P1[4]/ENET_TX_EN/T3_MAT2/SSP2_MISO_C6") (pintype "bidirectional"))
    )
    (net (code "43") (name "/EN_1V5") (class "Default")
      (node (ref "IC11") (pin "D7") (pinfunction "P1[9]/ENET_RXD0/T3_MAT0_D7") (pintype "bidirectional"))
    )
    (net (code "44") (name "/EN_1V8") (class "Default")
      (node (ref "IC11") (pin "B6") (pinfunction "P1[8]/ENET_CRS_(ENET_CRS_DV)/T3_MAT1/SSP2_SSEL_B6") (pintype "bidirectional"))
    )
    (net (code "45") (name "/EN_3V3") (class "Default")
      (node (ref "IC11") (pin "C13") (pinfunction "P1[7]/ENET_COL/SD_DAT[1]/PWM0[5]_C13") (pintype "bidirectional"))
    )
    (net (code "46") (name "/EN_FLASH_UPDATE") (class "Default")
      (node (ref "IC11") (pin "J4") (pinfunction "P0[12]/~{USB_PPWR2/SSP1}_MISO/ADC0_IN[6]_J4") (pintype "bidirectional"))
    )
    (net (code "47") (name "/EN_N3V5") (class "Default")
      (node (ref "IC11") (pin "D8") (pinfunction "P1[14]/ENET_RX_ER/T2_CAP0_D8") (pintype "bidirectional"))
    )
    (net (code "48") (name "/EN_P0V95") (class "Default")
      (node (ref "IC11") (pin "B13") (pinfunction "P1[5]/ENET_TX_ER/SD_PWR/PWM0[3]_B13") (pintype "bidirectional"))
    )
    (net (code "49") (name "/EN_P2V5") (class "Default")
      (node (ref "IC11") (pin "M9") (pinfunction "P1[27]/~{USB_INT1}/~{USB_OVRCR1}/T0_CAP1/CLKOUT_M9") (pintype "bidirectional"))
    )
    (net (code "50") (name "/EN_P3V3_CLK") (class "Default")
      (node (ref "IC11") (pin "D12") (pinfunction "P2[0]/PWM1[1]/U1_TXD_D12") (pintype "bidirectional"))
    )
    (net (code "51") (name "/EN_P4V0") (class "Default")
      (node (ref "IC11") (pin "P8") (pinfunction "P1[26]/~{USB_SSPND1}/PWM1[6]/T0_CAP0/MC_1B/SSP1_SSEL_P8") (pintype "bidirectional"))
    )
    (net (code "52") (name "/EN_P6V0") (class "Default")
      (node (ref "IC11") (pin "N10") (pinfunction "P1[29]/USB_SDA1/PWM1_CAP1/T0_MAT1/MC_2B/U4_TXD_N10") (pintype "bidirectional"))
    )
    (net (code "53") (name "/EN_PSU_CH") (class "Default")
      (node (ref "IC11") (pin "K2") (pinfunction "P1[31]/~{USB_OVRCR2}/SSP1_SCK/ADC0_IN[5]/I2C0_SCL_K2") (pintype "bidirectional"))
    )
    (net (code "54") (name "/EN_VCCINT") (class "Default")
      (node (ref "IC11") (pin "P10") (pinfunction "P1[28]/USB_SCL1/PWM1_CAP0/T0_MAT0/MC_2A/SSP0_SSEL_P10") (pintype "bidirectional"))
    )
    (net (code "55") (name "/FLASH_UPD_CLK") (class "Default")
      (node (ref "IC11") (pin "K6") (pinfunction "P1[20]/USB_TX_DP1/PWM1[2]/QEI_PHA/MC_FB0/SSP0_SCK_K6") (pintype "bidirectional"))
    )
    (net (code "56") (name "/FLASH_UPD_CSB") (class "Default")
      (node (ref "IC11") (pin "N6") (pinfunction "P1[21]/USB_TX_DM1/PWM1[3]/SSP0_SSEL/~{MC_ABORT}_N6") (pintype "bidirectional"))
    )
    (net (code "57") (name "/FLASH_UPD_MISO") (class "Default")
      (node (ref "IC11") (pin "N7") (pinfunction "P1[23]/USB_RX_DP1/PWM1[4]/QEI_PHB/MC_FB1/SSP0_MISO_N7") (pintype "bidirectional"))
    )
    (net (code "58") (name "/FLASH_UPD_MOSI") (class "Default")
      (node (ref "IC11") (pin "P7") (pinfunction "P1[24]/USB_RX_DM1/PWM1[5]/QEI_IDX/MC_FB2/SSP0_MOSI_P7") (pintype "bidirectional"))
    )
    (net (code "59") (name "/FPGA_I2C_SCL") (class "Default")
      (node (ref "R38") (pin "1") (pinfunction "1_1") (pintype "passive"))
    )
    (net (code "60") (name "/FPGA_I2C_SDA") (class "Default")
      (node (ref "R37") (pin "1") (pinfunction "1_1") (pintype "passive"))
    )
    (net (code "61") (name "/FPGA_RESETn") (class "Default")
      (node (ref "IC11") (pin "H12") (pinfunction "P4[9]/EMC_A[9]_H12") (pintype "bidirectional"))
      (node (ref "R44") (pin "2") (pinfunction "2_2") (pintype "passive"))
    )
    (net (code "62") (name "/FPGA_STATUS") (class "Default")
      (node (ref "IC11") (pin "M5") (pinfunction "P0[14]/~{USB_HSTEN2}/SSP1_SSEL/USB_CONNECT2_M5") (pintype "bidirectional"))
    )
    (net (code "63") (name "/GA0") (class "Default")
      (node (ref "D4") (pin "1") (pinfunction "C_1") (pintype "passive"))
      (node (ref "R47") (pin "1") (pinfunction "1_1") (pintype "passive"))
      (node (ref "R50") (pin "1") (pinfunction "1_1") (pintype "passive"))
    )
    (net (code "64") (name "/GA0_R") (class "Default")
      (node (ref "IC11") (pin "D6") (pinfunction "P3[0]/EMC_D[0]_D6") (pintype "bidirectional"))
      (node (ref "R50") (pin "2") (pinfunction "2_2") (pintype "passive"))
    )
    (net (code "65") (name "/GA1") (class "Default")
      (node (ref "D6") (pin "1") (pinfunction "C_1") (pintype "passive"))
      (node (ref "R48") (pin "1") (pinfunction "1_1") (pintype "passive"))
      (node (ref "R51") (pin "1") (pinfunction "1_1") (pintype "passive"))
    )
    (net (code "66") (name "/GA1_R") (class "Default")
      (node (ref "IC11") (pin "E6") (pinfunction "P3[1]/EMC_D[1]_E6") (pintype "bidirectional"))
      (node (ref "R51") (pin "2") (pinfunction "2_2") (pintype "passive"))
    )
    (net (code "67") (name "/GA2") (class "Default")
      (node (ref "D5") (pin "1") (pinfunction "C_1") (pintype "passive"))
      (node (ref "R49") (pin "1") (pinfunction "1_1") (pintype "passive"))
      (node (ref "R53") (pin "1") (pinfunction "1_1") (pintype "passive"))
    )
    (net (code "68") (name "/GA2_R") (class "Default")
      (node (ref "IC11") (pin "A2") (pinfunction "P3[2]/EMC_D[2]_A2") (pintype "bidirectional"))
      (node (ref "R53") (pin "2") (pinfunction "2_2") (pintype "passive"))
    )
    (net (code "69") (name "/I2C_MUX_ADDR1") (class "Default")
      (node (ref "IC11") (pin "L1") (pinfunction "P2[29]/EMC_DQM1_L1") (pintype "bidirectional"))
    )
    (net (code "70") (name "/I2C_MUX_ADDR2") (class "Default")
      (node (ref "IC11") (pin "M2") (pinfunction "P2[28]/EMC_DQM0_M2") (pintype "bidirectional"))
    )
    (net (code "72") (name "/I2C_SW_RESETn") (class "Default")
      (node (ref "IC11") (pin "E5") (pinfunction "P5[0]/EMC_A[24]/SSP2_MOSI/T2_MAT2_E5") (pintype "bidirectional"))
      (node (ref "R46") (pin "2") (pinfunction "2_2") (pintype "passive"))
    )
    (net (code "73") (name "/IPMB_SCL") (class "Default")
      (node (ref "D3") (pin "1") (pinfunction "C_1") (pintype "passive"))
      (node (ref "IC11") (pin "M1") (pinfunction "P0[28]/I2C0_SCL/USB_SCL1_M1") (pintype "bidirectional"))
      (node (ref "R45") (pin "2") (pinfunction "2_2") (pintype "passive"))
    )
    (net (code "74") (name "/IPMB_SDA") (class "Default")
      (node (ref "D2") (pin "1") (pinfunction "C_1") (pintype "passive"))
      (node (ref "IC11") (pin "L3") (pinfunction "P0[27]/I2C0_SDA/USB_SDA1_L3") (pintype "bidirectional"))
      (node (ref "R43") (pin "2") (pinfunction "2_2") (pintype "passive"))
    )
    (net (code "75") (name "/ISP_RSTn") (class "Default")
      (node (ref "SW1") (pin "1") (pinfunction "1_1") (pintype "bidirectional"))
    )
    (net (code "76") (name "/ISP_RSTn_SW") (class "Default")
      (node (ref "D8") (pin "1") (pinfunction "C_1") (pintype "passive"))
      (node (ref "SW1") (pin "8") (pinfunction "8_8") (pintype "bidirectional"))
    )
    (net (code "77") (name "/LPC_ISPn") (class "Default")
      (node (ref "SW1") (pin "2") (pinfunction "2_2") (pintype "bidirectional"))
    )
    (net (code "78") (name "/LPC_ISPn_SW") (class "Default")
      (node (ref "IC11") (pin "M13") (pinfunction "P2[10]/~{EINT0}/NMI_M13") (pintype "bidirectional"))
      (node (ref "SW1") (pin "7") (pinfunction "7_7") (pintype "bidirectional"))
    )
    (net (code "79") (name "/LPC_RST") (class "Default")
      (node (ref "D7") (pin "2") (pinfunction "A_2") (pintype "passive"))
      (node (ref "D8") (pin "2") (pinfunction "A_2") (pintype "passive"))
      (node (ref "IC11") (pin "J1") (pinfunction "~{RESET}_J1") (pintype "input"))
      (node (ref "J3") (pin "10") (pinfunction "10_10") (pintype "bidirectional"))
      (node (ref "R57") (pin "2") (pinfunction "2_2") (pintype "passive"))
    )
    (net (code "80") (name "/LTM_PGOOD") (class "Default")
      (node (ref "IC11") (pin "A7") (pinfunction "P1[10]/ENET_RXD1/T3_CAP0_A7") (pintype "bidirectional"))
    )
    (net (code "81") (name "/MMC_CONS_PROG_RxD") (class "Default")
      (node (ref "IC11") (pin "A3") (pinfunction "P0[3]/U0_RXD/U3_RXD_A3") (pintype "bidirectional"))
    )
    (net (code "82") (name "/MMC_CONS_PROG_TxD") (class "Default")
      (node (ref "IC11") (pin "D5") (pinfunction "P0[2]/U0_TXD/U3_TXD_D5") (pintype "bidirectional"))
    )
    (net (code "83") (name "/MMC_FPGA_DONE") (class "Default")
      (node (ref "IC11") (pin "B11") (pinfunction "P0[5]/I2S_RX_WS/CAN_TD2/T2_CAP1_B11") (pintype "bidirectional"))
    )
    (net (code "84") (name "/MMC_FPGA_INIT_B") (class "Default")
      (node (ref "IC11") (pin "J5") (pinfunction "P0[13]/USB_UP_LED2/SSP1_MOSI/ADC0_IN[7]_J5") (pintype "bidirectional"))
    )
    (net (code "85") (name "/MMC_FPGA_PROG_B") (class "Default")
      (node (ref "IC11") (pin "A11") (pinfunction "P0[4]/I2S_RX_SCK/CAN_RD2/T2_CAP0_A11") (pintype "bidirectional"))
    )
    (net (code "86") (name "/MMC_MISO1") (class "Default")
      (node (ref "IC11") (pin "C12") (pinfunction "P0[8]/I2S_TX_WS/SSP1_MISO/T2_MAT2/RTC_EV1_C12") (pintype "bidirectional"))
    )
    (net (code "87") (name "/MMC_MOSI1") (class "Default")
      (node (ref "IC11") (pin "A13") (pinfunction "P0[9]/I2S_TX_SDA/SSP1_MOSI/T2_MAT3/RTC_EV2_A13") (pintype "bidirectional"))
    )
    (net (code "88") (name "/MMC_RESETn") (class "Default")
      (node (ref "D7") (pin "1") (pinfunction "C_1") (pintype "passive"))
      (node (ref "IC12") (pin "1") (pinfunction "~{RESET}_1") (pintype "output"))
    )
    (net (code "89") (name "/MMC_SCK1") (class "Default")
      (node (ref "IC11") (pin "B12") (pinfunction "P0[7]/I2S_TX_SCK/SSP1_SCK/T2_MAT1/RTC_EV0_B12") (pintype "bidirectional"))
    )
    (net (code "90") (name "/MMC_SCL") (class "Default")
      (node (ref "IC11") (pin "N11") (pinfunction "P0[1]/CAN_TD1/U3_RXD/I2C1_SCL/U0_RXD_N11") (pintype "bidirectional"))
    )
    (net (code "91") (name "/MMC_SDA") (class "Default")
      (node (ref "IC11") (pin "M10") (pinfunction "P0[0]/CAN_RD1/U3_TXD/I2C1_SDA/U0_TXD_M10") (pintype "bidirectional"))
    )
    (net (code "92") (name "/MMC_SSEL1") (class "Default")
      (node (ref "IC11") (pin "D11") (pinfunction "P0[6]/I2S_RX_SDA/SSP1_SSEL/T2_MAT0/U1_RTS_D11") (pintype "bidirectional"))
    )
    (net (code "93") (name "/MMC_TCK") (class "Default")
      (node (ref "R60") (pin "1") (pinfunction "1_1") (pintype "passive"))
    )
    (net (code "94") (name "/MMC_TCK_SW") (class "Default")
      (node (ref "IC11") (pin "D2") (pinfunction "JTAG_TCK(SWDCLK)_D2") (pintype "input"))
      (node (ref "J3") (pin "4") (pinfunction "4_4") (pintype "bidirectional"))
      (node (ref "R56") (pin "2") (pinfunction "2_2") (pintype "passive"))
      (node (ref "R60") (pin "2") (pinfunction "2_2") (pintype "passive"))
    )
    (net (code "95") (name "/MMC_TDI") (class "Default")
      (node (ref "R61") (pin "1") (pinfunction "1_1") (pintype "passive"))
    )
    (net (code "96") (name "/MMC_TDI_SW") (class "Default")
      (node (ref "IC11") (pin "C3") (pinfunction "JTAG_TDI_C3") (pintype "input"))
      (node (ref "J3") (pin "8") (pinfunction "8_8") (pintype "bidirectional"))
      (node (ref "R61") (pin "2") (pinfunction "2_2") (pintype "passive"))
    )
    (net (code "97") (name "/MMC_TDO") (class "Default")
      (node (ref "R62") (pin "1") (pinfunction "1_1") (pintype "passive"))
    )
    (net (code "98") (name "/MMC_TDO_SW") (class "Default")
      (node (ref "IC11") (pin "B1") (pinfunction "JTAG_TDO(SWO)_B1") (pintype "output"))
      (node (ref "J3") (pin "6") (pinfunction "6_6") (pintype "bidirectional"))
      (node (ref "R62") (pin "2") (pinfunction "2_2") (pintype "passive"))
    )
    (net (code "99") (name "/MMC_TMS") (class "Default")
      (node (ref "R63") (pin "1") (pinfunction "1_1") (pintype "passive"))
    )
    (net (code "100") (name "/MMC_TMS_SW") (class "Default")
      (node (ref "IC11") (pin "C2") (pinfunction "JTAG_TMS(SWDIO)_C2") (pintype "bidirectional"))
      (node (ref "J3") (pin "2") (pinfunction "2_2") (pintype "bidirectional"))
      (node (ref "R59") (pin "2") (pinfunction "2_2") (pintype "passive"))
      (node (ref "R63") (pin "2") (pinfunction "2_2") (pintype "passive"))
    )
    (net (code "101") (name "/MMC_TRSTn") (class "Default")
      (node (ref "R64") (pin "1") (pinfunction "1_1") (pintype "passive"))
    )
    (net (code "102") (name "/MMC_TRSTn_SW") (class "Default")
      (node (ref "IC11") (pin "D4") (pinfunction "JTAG_~{TRST}_D4") (pintype "input"))
      (node (ref "R58") (pin "2") (pinfunction "2_2") (pintype "passive"))
      (node (ref "R64") (pin "2") (pinfunction "2_2") (pintype "passive"))
    )
    (net (code "103") (name "/MOD_HANDLE") (class "Default")
      (node (ref "IC11") (pin "B14") (pinfunction "P4[13]/EMC_A[13]_B14") (pintype "bidirectional"))
      (node (ref "R41") (pin "1") (pinfunction "1_1") (pintype "passive"))
    )
    (net (code "104") (name "/MP_XTAL1") (class "Default")
      (node (ref "C83") (pin "2") (pinfunction "2_2") (pintype "passive"))
      (node (ref "IC11") (pin "K4") (pinfunction "XTAL2_K4") (pintype "passive"))
      (node (ref "Q1") (pin "2") (pinfunction "OSC2_2") (pintype "passive"))
    )
    (net (code "105") (name "/MP_XTAL2") (class "Default")
      (node (ref "C82") (pin "2") (pinfunction "2_2") (pintype "passive"))
      (node (ref "IC11") (pin "L2") (pinfunction "XTAL1_L2") (pintype "passive"))
      (node (ref "Q1") (pin "1") (pinfunction "OSC1_1") (pintype "passive"))
    )
    (net (code "106") (name "/MRn") (class "Default")
      (node (ref "IC12") (pin "3") (pinfunction "~{MR}_3") (pintype "input"))
      (node (ref "R52") (pin "1") (pinfunction "1_1") (pintype "passive"))
      (node (ref "R54") (pin "2") (pinfunction "2_2") (pintype "passive"))
      (node (ref "SW1") (pin "5") (pinfunction "5_5") (pintype "bidirectional"))
    )
    (net (code "107") (name "/MRnR") (class "Default")
      (node (ref "R54") (pin "1") (pinfunction "1_1") (pintype "passive"))
      (node (ref "SW1") (pin "4") (pinfunction "4_4") (pintype "bidirectional"))
      (node (ref "T1") (pin "3") (pinfunction "D_3") (pintype "passive"))
    )
    (net (code "108") (name "/P0V95I_PG") (class "Default")
      (node (ref "IC11") (pin "D14") (pinfunction "P1[13]/ENET_RX_DV_D14") (pintype "bidirectional"))
    )
    (net (code "109") (name "/P0V95_PG") (class "Default")
      (node (ref "IC11") (pin "A12") (pinfunction "P1[11]/ENET_RXD2/SD_DAT[2]/PWM0[6]_A12") (pintype "bidirectional"))
    )
    (net (code "110") (name "/P1") (class "Default")
      (node (ref "IC11") (pin "G5") (pinfunction "P3[3]/EMC_D[3]_G5") (pintype "bidirectional"))
      (node (ref "R47") (pin "2") (pinfunction "2_2") (pintype "passive"))
      (node (ref "R48") (pin "2") (pinfunction "2_2") (pintype "passive"))
      (node (ref "R49") (pin "2") (pinfunction "2_2") (pintype "passive"))
    )
    (net (code "111") (name "/P1V2_PG") (class "Default")
      (node (ref "IC11") (pin "A14") (pinfunction "P1[12]/ENET_RXD3/SD_DAT[3]/PWM0_CAP0_A14") (pintype "bidirectional"))
    )
    (net (code "112") (name "/P2") (class "Default")
      (node (ref "IC11") (pin "D3") (pinfunction "P3[4]/EMC_D[4]_D3") (pintype "bidirectional"))
      (node (ref "R68") (pin "2") (pinfunction "2_2") (pintype "passive"))
    )
    (net (code "113") (name "/P2_BLUE") (class "Default")
      (node (ref "LD1") (pin "1") (pinfunction "C_1") (pintype "passive"))
      (node (ref "R68") (pin "1") (pinfunction "1_1") (pintype "passive"))
    )
    (net (code "114") (name "/P3") (class "Default")
      (node (ref "IC11") (pin "E3") (pinfunction "P3[5]/EMC_D[5]_E3") (pintype "bidirectional"))
      (node (ref "R70") (pin "2") (pinfunction "2_2") (pintype "passive"))
    )
    (net (code "115") (name "/P3V3MP_LAVCC") (class "Default")
      (node (ref "C81") (pin "1") (pinfunction "1_1") (pintype "passive"))
      (node (ref "IC11") (pin "F2") (pinfunction "VDDA_F2") (pintype "power_in"))
      (node (ref "IC11") (pin "G2") (pinfunction "VREFP_G2") (pintype "power_in"))
      (node (ref "L12") (pin "1") (pinfunction "1_1") (pintype "passive"))
    )
    (net (code "116") (name "/P3_GREEN") (class "Default")
      (node (ref "LD2") (pin "1") (pinfunction "C_1") (pintype "passive"))
      (node (ref "R70") (pin "1") (pinfunction "1_1") (pintype "passive"))
    )
    (net (code "117") (name "/P4") (class "Default")
      (node (ref "IC11") (pin "L7") (pinfunction "P1[25]/~{USB_LS1}/~{USB_HSTEN1}/T1_MAT1/MC_1A/CLKOUT_L7") (pintype "bidirectional"))
      (node (ref "R71") (pin "2") (pinfunction "2_2") (pintype "passive"))
    )
    (net (code "118") (name "/P4_RED") (class "Default")
      (node (ref "LD3") (pin "1") (pinfunction "C_1") (pintype "passive"))
      (node (ref "R71") (pin "1") (pinfunction "1_1") (pintype "passive"))
    )
    (net (code "119") (name "/P12V0_OK") (class "Default")
      (node (ref "IC11") (pin "N4") (pinfunction "P0[30]/USB_D-1/~{EINT1}_N4") (pintype "bidirectional"))
    )
    (net (code "120") (name "/PGOOD_N3V5") (class "Default")
      (node (ref "IC11") (pin "A8") (pinfunction "P1[15]/ENET_RX_CLK_(ENET_REF_CLK)/I2C2_SDA_A8") (pintype "bidirectional"))
    )
    (net (code "121") (name "/PGOOD_P2V5") (class "Default")
      (node (ref "IC11") (pin "L5") (pinfunction "P1[18]/USB_UP_LED1/PWM1[1]/T1_CAP0/SSP1_MISO_L5") (pintype "bidirectional"))
    )
    (net (code "122") (name "/PGOOD_P4V0") (class "Default")
      (node (ref "IC11") (pin "P5") (pinfunction "P1[19]/~{USB_TX_E1}/~{USB_PPWR1}/T1_CAP1/MC_0A/SSP1_SCK/U2_OE_P5") (pintype "bidirectional"))
    )
    (net (code "123") (name "/PGOOD_P6V0") (class "Default")
      (node (ref "IC11") (pin "M6") (pinfunction "P1[22]/USB_RCV1/USB_PWRD1/T1_MAT0/MC_0B/SSP1_MOSI_M6") (pintype "bidirectional"))
    )
    (net (code "124") (name "/PGOOD_VTT_DAC") (class "Default")
      (node (ref "IC11") (pin "K3") (pinfunction "P1[30]/USB_PWRD2/USB_VBUS/ADC0_IN[4]/I2C0_SDA/U3_OE_K3") (pintype "bidirectional"))
    )
    (net (code "125") (name "/SDCLK") (class "Default")
      (node (ref "IC11") (pin "J10") (pinfunction "P0[19]/U1_DSR/SD_CLK/I2C1_SDA_J10") (pintype "bidirectional"))
      (node (ref "TP1") (pin "1") (pinfunction "1_1") (pintype "bidirectional"))
    )
    (net (code "126") (name "/SDCMD") (class "Default")
      (node (ref "IC11") (pin "K14") (pinfunction "P0[20]/U1_DTR/SD_CMD/I2C1_SCL_K14") (pintype "bidirectional"))
      (node (ref "TP2") (pin "1") (pinfunction "1_1") (pintype "bidirectional"))
    )
    (net (code "127") (name "/SDDAT0") (class "Default")
      (node (ref "IC11") (pin "L14") (pinfunction "P0[22]/U1_RTS/SD_DAT[0]/U4_TXD/CAN_TD1_L14") (pintype "bidirectional"))
      (node (ref "TP4") (pin "1") (pinfunction "1_1") (pintype "bidirectional"))
    )
    (net (code "128") (name "/SDDAT1") (class "Default")
      (node (ref "IC11") (pin "M12") (pinfunction "P2[11]/~{EINT1}/SD_DAT[1]/I2S_TX_SCK_M12") (pintype "bidirectional"))
      (node (ref "TP5") (pin "1") (pinfunction "1_1") (pintype "bidirectional"))
    )
    (net (code "129") (name "/SDDAT2") (class "Default")
      (node (ref "IC11") (pin "N14") (pinfunction "P2[12]/~{EINT2}/SD_DAT[2]/I2S_TX_WS_N14") (pintype "bidirectional"))
      (node (ref "TP6") (pin "1") (pinfunction "1_1") (pintype "bidirectional"))
    )
    (net (code "130") (name "/SDDAT3") (class "Default")
      (node (ref "IC11") (pin "M11") (pinfunction "P2[13]/~{EINT3}/SD_DAT[3]/I2S_TX_SDA_M11") (pintype "bidirectional"))
      (node (ref "TP7") (pin "1") (pinfunction "1_1") (pintype "bidirectional"))
    )
    (net (code "131") (name "/SDPWR") (class "Default")
      (node (ref "IC11") (pin "K11") (pinfunction "P0[21]/U1_RI/SD_PWR/U4_OE/CAN_RD1/U4_SCLK_K11") (pintype "bidirectional"))
      (node (ref "TP3") (pin "1") (pinfunction "1_1") (pintype "bidirectional"))
    )
    (net (code "132") (name "/SDRAM_PGOOD") (class "Default")
      (node (ref "IC11") (pin "E14") (pinfunction "P2[4]/PWM1[5]/U1_DSR/T2_MAT1/TRACEDATA[1]_E14") (pintype "bidirectional"))
    )
    (net (code "133") (name "/SSP0_MISO") (class "Default")
      (node (ref "IC11") (pin "J12") (pinfunction "P0[17]/U1_CTS/SSP0_MISO_J12") (pintype "bidirectional"))
    )
    (net (code "134") (name "/SSP0_MOSI") (class "Default")
      (node (ref "IC11") (pin "J13") (pinfunction "P0[18]/U1_DCD/SSP0_MOSI_J13") (pintype "bidirectional"))
    )
    (net (code "135") (name "/SSP0_SCK") (class "Default")
      (node (ref "IC11") (pin "H13") (pinfunction "P0[15]/U1_TXD/SSP0_SCK_H13") (pintype "bidirectional"))
    )
    (net (code "136") (name "/SSP0_SSEL") (class "Default")
      (node (ref "IC11") (pin "H14") (pinfunction "P0[16]/U1_RXD/SSP0_SSEL_H14") (pintype "bidirectional"))
    )
    (net (code "137") (name "/SW") (class "Default")
      (node (ref "IC11") (pin "F10") (pinfunction "P4[12]/EMC_A[12]_F10") (pintype "bidirectional"))
      (node (ref "R40") (pin "1") (pinfunction "1_1") (pintype "passive"))
    )
    (net (code "147") (name "GND") (class "Default")
      (node (ref "C100") (pin "2") (pinfunction "2_2") (pintype "passive"))
      (node (ref "C101") (pin "2") (pinfunction "2_2") (pintype "passive"))
      (node (ref "C80") (pin "1") (pinfunction "1_1") (pintype "passive"))
      (node (ref "C81") (pin "2") (pinfunction "2_2") (pintype "passive"))
      (node (ref "C82") (pin "1") (pinfunction "1_1") (pintype "passive"))
      (node (ref "C83") (pin "1") (pinfunction "1_1") (pintype "passive"))
      (node (ref "C84") (pin "2") (pinfunction "2_2") (pintype "passive"))
      (node (ref "C85") (pin "2") (pinfunction "2_2") (pintype "passive"))
      (node (ref "C86") (pin "2") (pinfunction "2_2") (pintype "passive"))
      (node (ref "C87") (pin "2") (pinfunction "2_2") (pintype "passive"))
      (node (ref "C88") (pin "2") (pinfunction "2_2") (pintype "passive"))
      (node (ref "C89") (pin "2") (pinfunction "2_2") (pintype "passive"))
      (node (ref "C90") (pin "2") (pinfunction "2_2") (pintype "passive"))
      (node (ref "C91") (pin "2") (pinfunction "2_2") (pintype "passive"))
      (node (ref "C92") (pin "2") (pinfunction "2_2") (pintype "passive"))
      (node (ref "C93") (pin "2") (pinfunction "2_2") (pintype "passive"))
      (node (ref "C94") (pin "2") (pinfunction "2_2") (pintype "passive"))
      (node (ref "C95") (pin "2") (pinfunction "2_2") (pintype "passive"))
      (node (ref "C96") (pin "2") (pinfunction "2_2") (pintype "passive"))
      (node (ref "C97") (pin "2") (pinfunction "2_2") (pintype "passive"))
      (node (ref "C98") (pin "2") (pinfunction "2_2") (pintype "passive"))
      (node (ref "C99") (pin "2") (pinfunction "2_2") (pintype "passive"))
      (node (ref "D2") (pin "2") (pinfunction "A_2") (pintype "passive"))
      (node (ref "D3") (pin "2") (pinfunction "A_2") (pintype "passive"))
      (node (ref "D4") (pin "2") (pinfunction "A_2") (pintype "passive"))
      (node (ref "D5") (pin "2") (pinfunction "A_2") (pintype "passive"))
      (node (ref "D6") (pin "2") (pinfunction "A_2") (pintype "passive"))
      (node (ref "D9") (pin "2") (pinfunction "A_2") (pintype "passive"))
      (node (ref "IC11") (pin "A10") (pinfunction "VSSREG_A10") (pintype "power_in"))
      (node (ref "IC11") (pin "B4") (pinfunction "VSS_B4") (pintype "power_in"))
      (node (ref "IC11") (pin "C11") (pinfunction "VSS_C11") (pintype "power_in"))
      (node (ref "IC11") (pin "D13") (pinfunction "VSS_D13") (pintype "power_in"))
      (node (ref "IC11") (pin "F3") (pinfunction "VSSA_F3") (pintype "power_in"))
      (node (ref "IC11") (pin "G13") (pinfunction "VSS_G13") (pintype "power_in"))
      (node (ref "IC11") (pin "H3") (pinfunction "VSSREG_H3") (pintype "power_in"))
      (node (ref "IC11") (pin "H4") (pinfunction "VSS_H4") (pintype "power_in"))
      (node (ref "IC11") (pin "L13") (pinfunction "VSS_L13") (pintype "power_in"))
      (node (ref "IC11") (pin "L8") (pinfunction "VSSREG_L8") (pintype "power_in"))
      (node (ref "IC11") (pin "L9") (pinfunction "VSS_L9") (pintype "power_in"))
      (node (ref "IC11") (pin "P4") (pinfunction "VSS_P4") (pintype "power_in"))
      (node (ref "IC12") (pin "2") (pinfunction "GND_2") (pintype "power_in"))
      (node (ref "J3") (pin "3") (pinfunction "3_3") (pintype "bidirectional"))
      (node (ref "J3") (pin "5") (pinfunction "5_5") (pintype "bidirectional"))
      (node (ref "J3") (pin "9") (pinfunction "9_9") (pintype "bidirectional"))
      (node (ref "R44") (pin "1") (pinfunction "1_1") (pintype "passive"))
      (node (ref "R56") (pin "1") (pinfunction "1_1") (pintype "passive"))
      (node (ref "R72") (pin "1") (pinfunction "1_1") (pintype "passive"))
      (node (ref "R73") (pin "1") (pinfunction "1_1") (pintype "passive"))
      (node (ref "R74") (pin "1") (pinfunction "1_1") (pintype "passive"))
      (node (ref "R75") (pin "1") (pinfunction "1_1") (pintype "passive"))
      (node (ref "T1") (pin "2") (pinfunction "S_2") (pintype "passive"))
    )
    (net (code "148") (name "Net-(IC11A-P0[10]{slash}U2_TXD{slash}I2C2_SDA{slash}T3_MAT0)") (class "Default")
      (node (ref "IC11") (pin "L10") (pinfunction "P0[10]/U2_TXD/I2C2_SDA/T3_MAT0_L10") (pintype "bidirectional"))
      (node (ref "R37") (pin "2") (pinfunction "2_2") (pintype "passive"))
    )
    (net (code "149") (name "Net-(IC11A-P0[11]{slash}U2_RXD{slash}I2C2_SCL{slash}T3_MAT1)") (class "Default")
      (node (ref "IC11") (pin "P12") (pinfunction "P0[11]/U2_RXD/I2C2_SCL/T3_MAT1_P12") (pintype "bidirectional"))
      (node (ref "R38") (pin "2") (pinfunction "2_2") (pintype "passive"))
    )
    (net (code "150") (name "Net-(IC12-CT)") (class "Default")
      (node (ref "C80") (pin "2") (pinfunction "2_2") (pintype "passive"))
      (node (ref "IC12") (pin "4") (pinfunction "CT_4") (pintype "passive"))
    )
    (net (code "151") (name "P3V3MP") (class "Default")
      (node (ref "C100") (pin "1") (pinfunction "1_1") (pintype "passive"))
      (node (ref "C101") (pin "1") (pinfunction "1_1") (pintype "passive"))
      (node (ref "C84") (pin "1") (pinfunction "1_1") (pintype "passive"))
      (node (ref "C85") (pin "1") (pinfunction "1_1") (pintype "passive"))
      (node (ref "C86") (pin "1") (pinfunction "1_1") (pintype "passive"))
      (node (ref "C87") (pin "1") (pinfunction "1_1") (pintype "passive"))
      (node (ref "C88") (pin "1") (pinfunction "1_1") (pintype "passive"))
      (node (ref "C89") (pin "1") (pinfunction "1_1") (pintype "passive"))
      (node (ref "C90") (pin "1") (pinfunction "1_1") (pintype "passive"))
      (node (ref "C91") (pin "1") (pinfunction "1_1") (pintype "passive"))
      (node (ref "C92") (pin "1") (pinfunction "1_1") (pintype "passive"))
      (node (ref "C93") (pin "1") (pinfunction "1_1") (pintype "passive"))
      (node (ref "C94") (pin "1") (pinfunction "1_1") (pintype "passive"))
      (node (ref "C95") (pin "1") (pinfunction "1_1") (pintype "passive"))
      (node (ref "C96") (pin "1") (pinfunction "1_1") (pintype "passive"))
      (node (ref "C97") (pin "1") (pinfunction "1_1") (pintype "passive"))
      (node (ref "C98") (pin "1") (pinfunction "1_1") (pintype "passive"))
      (node (ref "C99") (pin "1") (pinfunction "1_1") (pintype "passive"))
      (node (ref "IC11") (pin "C5") (pinfunction "VDD(3V3)_C5") (pintype "power_in"))
      (node (ref "IC11") (pin "E10") (pinfunction "VDD(3V3)_E10") (pintype "power_in"))
      (node (ref "IC11") (pin "E12") (pinfunction "VDD(3V3)_E12") (pintype "power_in"))
      (node (ref "IC11") (pin "E2") (pinfunction "VDD(3V3)_E2") (pintype "power_in"))
      (node (ref "IC11") (pin "E9") (pinfunction "VDD(REG)(3V3)_E9") (pintype "power_in"))
      (node (ref "IC11") (pin "G1") (pinfunction "VDD(REG)(3V3)_G1") (pintype "power_in"))
      (node (ref "IC11") (pin "J14") (pinfunction "VDD(3V3)_J14") (pintype "power_in"))
      (node (ref "IC11") (pin "K1") (pinfunction "VBAT_K1") (pintype "power_in"))
      (node (ref "IC11") (pin "K8") (pinfunction "VDD(3V3)_K8") (pintype "power_in"))
      (node (ref "IC11") (pin "L11") (pinfunction "VDD(3V3)_L11") (pintype "power_in"))
      (node (ref "IC11") (pin "L4") (pinfunction "VDD(3V3)_L4") (pintype "power_in"))
      (node (ref "IC11") (pin "N9") (pinfunction "VDD(REG)(3V3)_N9") (pintype "power_in"))
      (node (ref "IC12") (pin "5") (pinfunction "SENSE_5") (pintype "input"))
      (node (ref "IC12") (pin "6") (pinfunction "VDD_6") (pintype "power_in"))
      (node (ref "J3") (pin "1") (pinfunction "1_1") (pintype "bidirectional"))
      (node (ref "L12") (pin "2") (pinfunction "2_2") (pintype "passive"))
      (node (ref "LD1") (pin "2") (pinfunction "A_2") (pintype "passive"))
      (node (ref "LD2") (pin "2") (pinfunction "A_2") (pintype "passive"))
      (node (ref "LD3") (pin "2") (pinfunction "A_2") (pintype "passive"))
      (node (ref "R39") (pin "2") (pinfunction "2_2") (pintype "passive"))
      (node (ref "R40") (pin "2") (pinfunction "2_2") (pintype "passive"))
      (node (ref "R41") (pin "2") (pinfunction "2_2") (pintype "passive"))
      (node (ref "R43") (pin "1") (pinfunction "1_1") (pintype "passive"))
      (node (ref "R45") (pin "1") (pinfunction "1_1") (pintype "passive"))
      (node (ref "R46") (pin "1") (pinfunction "1_1") (pintype "passive"))
      (node (ref "R52") (pin "2") (pinfunction "2_2") (pintype "passive"))
      (node (ref "R55") (pin "2") (pinfunction "2_2") (pintype "passive"))
      (node (ref "R57") (pin "1") (pinfunction "1_1") (pintype "passive"))
      (node (ref "R58") (pin "1") (pinfunction "1_1") (pintype "passive"))
      (node (ref "R59") (pin "1") (pinfunction "1_1") (pintype "passive"))
      (node (ref "R65") (pin "1") (pinfunction "1_1") (pintype "passive"))
      (node (ref "R66") (pin "1") (pinfunction "1_1") (pintype "passive"))
      (node (ref "R67") (pin "1") (pinfunction "1_1") (pintype "passive"))
      (node (ref "R69") (pin "1") (pinfunction "1_1") (pintype "passive"))
    )
    (net (code "152") (name "unconnected-(IC11A-P0[23]{slash}ADC0_IN[0]{slash}I2S_RX_SCK{slash}T3_CAP0-PadF5)") (class "Default")
      (node (ref "IC11") (pin "F5") (pinfunction "P0[23]/ADC0_IN[0]/I2S_RX_SCK/T3_CAP0_F5") (pintype "bidirectional"))
    )
    (net (code "153") (name "unconnected-(IC11A-P0[24]{slash}ADC0_IN[1]{slash}I2S_RX_WS{slash}T3_CAP1-PadE1)") (class "Default")
      (node (ref "IC11") (pin "E1") (pinfunction "P0[24]/ADC0_IN[1]/I2S_RX_WS/T3_CAP1_E1") (pintype "bidirectional+no_connect"))
    )
    (net (code "154") (name "unconnected-(IC11A-P0[25]{slash}ADC0_IN[2]{slash}I2S_RX_SDA{slash}U3_TXD-PadE4)") (class "Default")
      (node (ref "IC11") (pin "E4") (pinfunction "P0[25]/ADC0_IN[2]/I2S_RX_SDA/U3_TXD_E4") (pintype "bidirectional+no_connect"))
    )
    (net (code "155") (name "unconnected-(IC11A-P0[26]{slash}ADC0_IN[3]{slash}DAC_OUT{slash}U3_RXD-PadD1)") (class "Default")
      (node (ref "IC11") (pin "D1") (pinfunction "P0[26]/ADC0_IN[3]/DAC_OUT/U3_RXD_D1") (pintype "bidirectional+no_connect"))
    )
    (net (code "156") (name "unconnected-(IC11A-P0[29]{slash}USB_D+1{slash}~{EINT0}-PadK5)") (class "Default")
      (node (ref "IC11") (pin "K5") (pinfunction "P0[29]/USB_D+1/~{EINT0}_K5") (pintype "bidirectional+no_connect"))
    )
    (net (code "157") (name "unconnected-(IC11A-P0[31]{slash}USB_D+2-PadN1)") (class "Default")
      (node (ref "IC11") (pin "N1") (pinfunction "P0[31]/USB_D+2_N1") (pintype "bidirectional"))
    )
    (net (code "158") (name "unconnected-(IC11A-P1[0]{slash}ENET_TXD0{slash}T3_CAP1{slash}SSP2_SCK-PadB5)") (class "Default")
      (node (ref "IC11") (pin "B5") (pinfunction "P1[0]/ENET_TXD0/T3_CAP1/SSP2_SCK_B5") (pintype "bidirectional+no_connect"))
    )
    (net (code "159") (name "unconnected-(IC11A-P1[1]{slash}ENET_TXD1{slash}T3_MAT3{slash}SSP2_MOSI-PadA5)") (class "Default")
      (node (ref "IC11") (pin "A5") (pinfunction "P1[1]/ENET_TXD1/T3_MAT3/SSP2_MOSI_A5") (pintype "bidirectional+no_connect"))
    )
    (net (code "160") (name "unconnected-(IC11A-P1[2]{slash}ENET_TXD2{slash}SD_CLK{slash}PWM0[1]-PadB7)") (class "Default")
      (node (ref "IC11") (pin "B7") (pinfunction "P1[2]/ENET_TXD2/SD_CLK/PWM0[1]_B7") (pintype "bidirectional+no_connect"))
    )
    (net (code "161") (name "unconnected-(IC11A-P1[3]{slash}ENET_TXD3{slash}SD_CMD{slash}PWM0[2]-PadA9)") (class "Default")
      (node (ref "IC11") (pin "A9") (pinfunction "P1[3]/ENET_TXD3/SD_CMD/PWM0[2]_A9") (pintype "bidirectional+no_connect"))
    )
    (net (code "162") (name "unconnected-(IC11A-P1[16]{slash}ENET_MDC{slash}I2S_TX_MCLK-PadB8)") (class "Default")
      (node (ref "IC11") (pin "B8") (pinfunction "P1[16]/ENET_MDC/I2S_TX_MCLK_B8") (pintype "bidirectional"))
    )
    (net (code "163") (name "unconnected-(IC11A-P1[17]{slash}ENET_MDIO{slash}I2S_RX_MCLK-PadC9)") (class "Default")
      (node (ref "IC11") (pin "C9") (pinfunction "P1[17]/ENET_MDIO/I2S_RX_MCLK_C9") (pintype "bidirectional"))
    )
    (net (code "164") (name "unconnected-(IC11B-P2[1]{slash}PWM1[2]{slash}U1_RXD-PadC14)") (class "Default")
      (node (ref "IC11") (pin "C14") (pinfunction "P2[1]/PWM1[2]/U1_RXD_C14") (pintype "bidirectional"))
    )
    (net (code "165") (name "unconnected-(IC11B-P2[2]{slash}PWM1[3]{slash}U1_CTS{slash}T2_MAT3{slash}TRACEDATA[3]-PadE11)") (class "Default")
      (node (ref "IC11") (pin "E11") (pinfunction "P2[2]/PWM1[3]/U1_CTS/T2_MAT3/TRACEDATA[3]_E11") (pintype "bidirectional"))
    )
    (net (code "166") (name "unconnected-(IC11B-P2[3]{slash}PWM1[4]{slash}U1_DCD{slash}T2_MAT2{slash}TRACEDATA[2]-PadE13)") (class "Default")
      (node (ref "IC11") (pin "E13") (pinfunction "P2[3]/PWM1[4]/U1_DCD/T2_MAT2/TRACEDATA[2]_E13") (pintype "bidirectional+no_connect"))
    )
    (net (code "167") (name "unconnected-(IC11B-P2[5]{slash}PWM1[6]{slash}U1_DTR{slash}T2_MAT0{slash}TRACEDATA[0]-PadF12)") (class "Default")
      (node (ref "IC11") (pin "F12") (pinfunction "P2[5]/PWM1[6]/U1_DTR/T2_MAT0/TRACEDATA[0]_F12") (pintype "bidirectional+no_connect"))
    )
    (net (code "168") (name "unconnected-(IC11B-P2[6]{slash}PWM1_CAP0{slash}U1_RI{slash}T2_CAP0{slash}U2_OE{slash}TRACECLK-PadF13)") (class "Default")
      (node (ref "IC11") (pin "F13") (pinfunction "P2[6]/PWM1_CAP0/U1_RI/T2_CAP0/U2_OE/TRACECLK_F13") (pintype "bidirectional+no_connect"))
    )
    (net (code "169") (name "unconnected-(IC11B-P2[7]{slash}CAN_RD2{slash}U1_RTS-PadG11)") (class "Default")
      (node (ref "IC11") (pin "G11") (pinfunction "P2[7]/CAN_RD2/U1_RTS_G11") (pintype "bidirectional+no_connect"))
    )
    (net (code "170") (name "unconnected-(IC11B-P2[8]{slash}CAN_TD2{slash}U2_TXD{slash}U1_CTS{slash}ENET_MDC-PadG14)") (class "Default")
      (node (ref "IC11") (pin "G14") (pinfunction "P2[8]/CAN_TD2/U2_TXD/U1_CTS/ENET_MDC_G14") (pintype "bidirectional+no_connect"))
    )
    (net (code "171") (name "unconnected-(IC11B-P2[9]{slash}USB_CONNECT1{slash}U2_RXD{slash}U4_RXD{slash}ENET_MDIO-PadH11)") (class "Default")
      (node (ref "IC11") (pin "H11") (pinfunction "P2[9]/USB_CONNECT1/U2_RXD/U4_RXD/ENET_MDIO_H11") (pintype "bidirectional+no_connect"))
    )
    (net (code "172") (name "unconnected-(IC11B-P2[20]{slash}~{EMC_DYCS0}-PadP6)") (class "Default")
      (node (ref "IC11") (pin "P6") (pinfunction "P2[20]/~{EMC_DYCS0}_P6") (pintype "bidirectional+no_connect"))
    )
    (net (code "173") (name "unconnected-(IC11B-P2[21]{slash}~{EMC_DYCS1}-PadN8)") (class "Default")
      (node (ref "IC11") (pin "N8") (pinfunction "P2[21]/~{EMC_DYCS1}_N8") (pintype "bidirectional+no_connect"))
    )
    (net (code "174") (name "unconnected-(IC11B-P2[24]{slash}EMC_CKE0-PadP1)") (class "Default")
      (node (ref "IC11") (pin "P1") (pinfunction "P2[24]/EMC_CKE0_P1") (pintype "bidirectional+no_connect"))
    )
    (net (code "175") (name "unconnected-(IC11B-P2[25]{slash}EMC_CKE1-PadP2)") (class "Default")
      (node (ref "IC11") (pin "P2") (pinfunction "P2[25]/EMC_CKE1_P2") (pintype "bidirectional+no_connect"))
    )
    (net (code "176") (name "unconnected-(IC11B-P3[6]{slash}EMC_D[6]-PadF4)") (class "Default")
      (node (ref "IC11") (pin "F4") (pinfunction "P3[6]/EMC_D[6]_F4") (pintype "bidirectional+no_connect"))
    )
    (net (code "177") (name "unconnected-(IC11B-P3[7]{slash}EMC_D[7]-PadG3)") (class "Default")
      (node (ref "IC11") (pin "G3") (pinfunction "P3[7]/EMC_D[7]_G3") (pintype "bidirectional+no_connect"))
    )
    (net (code "178") (name "unconnected-(IC11B-P3[8]{slash}EMC_D[8]-PadA6)") (class "Default")
      (node (ref "IC11") (pin "A6") (pinfunction "P3[8]/EMC_D[8]_A6") (pintype "bidirectional+no_connect"))
    )
    (net (code "179") (name "unconnected-(IC11B-P3[9]{slash}EMC_D[9]-PadA4)") (class "Default")
      (node (ref "IC11") (pin "A4") (pinfunction "P3[9]/EMC_D[9]_A4") (pintype "bidirectional+no_connect"))
    )
    (net (code "180") (name "unconnected-(IC11B-P3[10]{slash}EMC_D[10]-PadB3)") (class "Default")
      (node (ref "IC11") (pin "B3") (pinfunction "P3[10]/EMC_D[10]_B3") (pintype "bidirectional+no_connect"))
    )
    (net (code "181") (name "unconnected-(IC11B-P3[11]{slash}EMC_D[11]-PadB2)") (class "Default")
      (node (ref "IC11") (pin "B2") (pinfunction "P3[11]/EMC_D[11]_B2") (pintype "bidirectional+no_connect"))
    )
    (net (code "182") (name "unconnected-(IC11B-P3[12]{slash}EMC_D[12]-PadA1)") (class "Default")
      (node (ref "IC11") (pin "A1") (pinfunction "P3[12]/EMC_D[12]_A1") (pintype "bidirectional+no_connect"))
    )
    (net (code "183") (name "unconnected-(IC11B-P3[13]{slash}EMC_D[13]-PadC1)") (class "Default")
      (node (ref "IC11") (pin "C1") (pinfunction "P3[13]/EMC_D[13]_C1") (pintype "bidirectional+no_connect"))
    )
    (net (code "184") (name "unconnected-(IC11B-P3[14]{slash}EMC_D[14]-PadF1)") (class "Default")
      (node (ref "IC11") (pin "F1") (pinfunction "P3[14]/EMC_D[14]_F1") (pintype "bidirectional+no_connect"))
    )
    (net (code "185") (name "unconnected-(IC11B-P3[15]{slash}EMC_D[15]-PadG4)") (class "Default")
      (node (ref "IC11") (pin "G4") (pinfunction "P3[15]/EMC_D[15]_G4") (pintype "bidirectional+no_connect"))
    )
    (net (code "186") (name "unconnected-(IC11C-P4[10]{slash}EMC_A[10]-PadG12)") (class "Default")
      (node (ref "IC11") (pin "G12") (pinfunction "P4[10]/EMC_A[10]_G12") (pintype "bidirectional+no_connect"))
    )
    (net (code "187") (name "unconnected-(IC11C-P4[28]{slash}~{EMC_BLS2}{slash}U3_TXD{slash}T2_MAT0-PadD10)") (class "Default")
      (node (ref "IC11") (pin "D10") (pinfunction "P4[28]/~{EMC_BLS2}/U3_TXD/T2_MAT0_D10") (pintype "bidirectional"))
    )
    (net (code "188") (name "unconnected-(IC11C-P4[29]{slash}~{EMC_BLS3}{slash}U3_RXD{slash}T2_MAT1{slash}I2C2_SCL-PadB9)") (class "Default")
      (node (ref "IC11") (pin "B9") (pinfunction "P4[29]/~{EMC_BLS3}/U3_RXD/T2_MAT1/I2C2_SCL_B9") (pintype "bidirectional"))
    )
    (net (code "189") (name "unconnected-(IC11C-P4[30]{slash}~{EMC_CS0}-PadC7)") (class "Default")
      (node (ref "IC11") (pin "C7") (pinfunction "P4[30]/~{EMC_CS0}_C7") (pintype "bidirectional"))
    )
    (net (code "190") (name "unconnected-(IC11C-P4[31]{slash}~{EMC_CS1}-PadE7)") (class "Default")
      (node (ref "IC11") (pin "E7") (pinfunction "P4[31]/~{EMC_CS1}_E7") (pintype "bidirectional"))
    )
    (net (code "191") (name "unconnected-(IC11C-P5[1]{slash}EMC_A[25]{slash}SSP2_MISO{slash}T2_MAT3-PadH1)") (class "Default")
      (node (ref "IC11") (pin "H1") (pinfunction "P5[1]/EMC_A[25]/SSP2_MISO/T2_MAT3_H1") (pintype "bidirectional+no_connect"))
    )
    (net (code "192") (name "unconnected-(IC11C-P5[2]{slash}T3_MAT2{slash}I2C0_SDA-PadL12)") (class "Default")
      (node (ref "IC11") (pin "L12") (pinfunction "P5[2]/T3_MAT2/I2C0_SDA_L12") (pintype "bidirectional+no_connect"))
    )
    (net (code "193") (name "unconnected-(IC11C-P5[3]{slash}U4_RXD{slash}I2C0_SCL-PadG10)") (class "Default")
      (node (ref "IC11") (pin "G10") (pinfunction "P5[3]/U4_RXD/I2C0_SCL_G10") (pintype "bidirectional+no_connect"))
    )
    (net (code "194") (name "unconnected-(IC11C-P5[4]{slash}U0_OE{slash}T3_MAT3{slash}U4_TXD-PadC4)") (class "Default")
      (node (ref "IC11") (pin "C4") (pinfunction "P5[4]/U0_OE/T3_MAT3/U4_TXD_C4") (pintype "bidirectional+no_connect"))
    )
    (net (code "195") (name "unconnected-(IC11D-RTCX1-PadJ2)") (class "Default")
      (node (ref "IC11") (pin "J2") (pinfunction "RTCX1_J2") (pintype "input+no_connect"))
    )
    (net (code "196") (name "unconnected-(IC11D-RTCX2-PadJ3)") (class "Default")
      (node (ref "IC11") (pin "J3") (pinfunction "RTCX2_J3") (pintype "output+no_connect"))
    )
    (net (code "197") (name "unconnected-(IC11D-RTC_ALARM-PadH5)") (class "Default")
      (node (ref "IC11") (pin "H5") (pinfunction "RTC_ALARM_H5") (pintype "output+no_connect"))
    )
    (net (code "198") (name "unconnected-(IC11D-USB_D-2-PadN2)") (class "Default")
      (node (ref "IC11") (pin "N2") (pinfunction "USB_D-2_N2") (pintype "bidirectional+no_connect"))
    )
    (net (code "199") (name "unconnected-(IC11D-~{RSTOUT}-PadH2)") (class "Default")
      (node (ref "IC11") (pin "H2") (pinfunction "~{RSTOUT}_H2") (pintype "output+no_connect"))
    )
    (net (code "200") (name "unconnected-(J3-Pad7)") (class "Default")
      (node (ref "J3") (pin "7") (pinfunction "7_7") (pintype "bidirectional"))
    )
    (net (code "201") (name "unconnected-(SW1-Pad3)") (class "Default")
      (node (ref "SW1") (pin "3") (pinfunction "3_3") (pintype "bidirectional"))
    )
    (net (code "202") (name "unconnected-(SW1-Pad6)") (class "Default")
      (node (ref "SW1") (pin "6") (pinfunction "6_6") (pintype "bidirectional"))
    )
  )
)
